# 55_VO-HDMI1_4_TX_MIPI_to_HDMI.net
KiCad netlist of a schematic drawn in Altium Designer
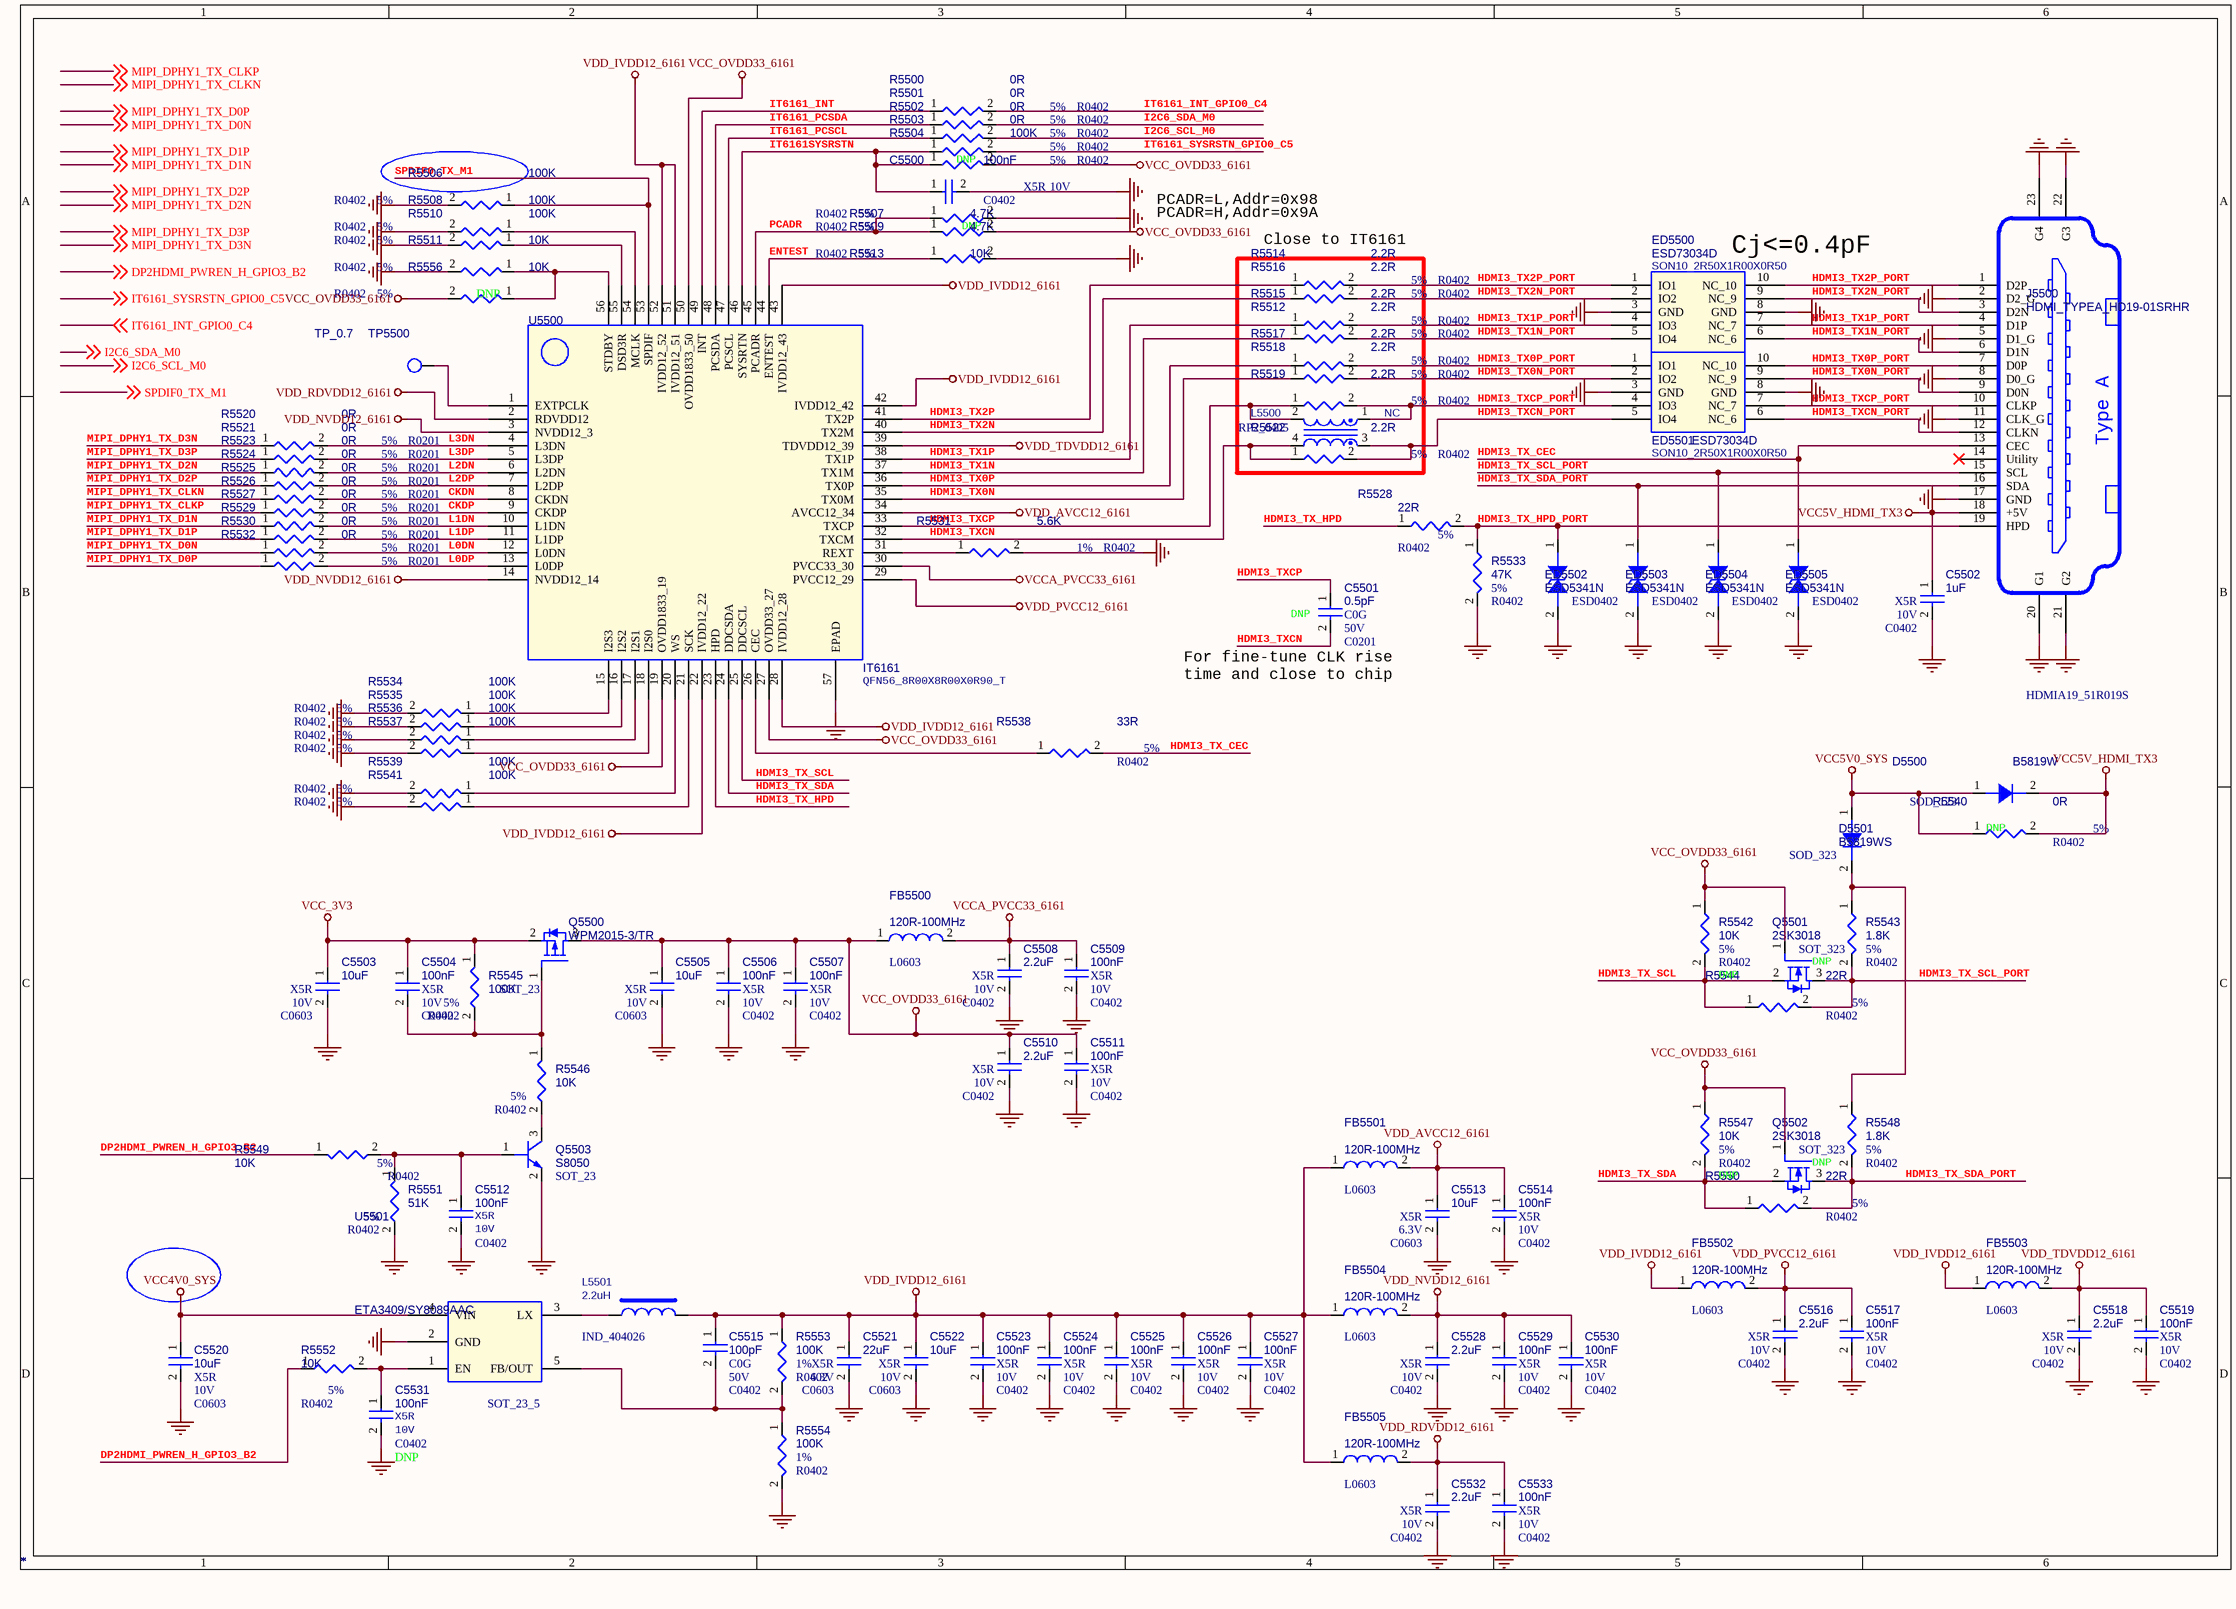
[diagram p0: 55.VO-HDMI1.4 TX(MIPI to HDMI).SchDoc]

(export (version "E")
  (design (tool "Eeschema 10.0.6"))
  (components
    (comp (ref "C5500")
      (value "*")
      (footprint "C0402")
      (description "cap,100.00nF,+/-10%,10V,X5R,C0402")
      (fields
        (field (name "VOLTAGE") "10V")
        (field (name "PCB FOOTPRINT") "C0402")
        (field (name "DIELECTRIC") "X5R")
        (field (name "MANUFACTURER") "TDK")
        (field (name "TOLERANCE") "10%")
        (field (name "ALTIUM_UNNAMED_1") "100nF")
        (field (name "CREATED BY") "JJJ")
      )
      (libsource (lib "*") (part "CAP NP"))
    )
    (comp (ref "C5501")
      (value "*")
      (footprint "C0201")
      (description "cap,0.50pF,+/-0.25,50V,C0G,C0201")
      (fields
        (field (name "VOLTAGE") "50V")
        (field (name "PCB FOOTPRINT") "C0201")
        (field (name "DIELECTRIC") "C0G")
        (field (name "OPTION") "DNP")
        (field (name "TOLERANCE") "+/-0.25pF")
        (field (name "MANUFACTURER") "TDK")
        (field (name "ALTIUM_UNNAMED_1") "0.5pF")
        (field (name "CREATED BY") "JJJ")
      )
      (libsource (lib "*") (part "CAP NP"))
    )
    (comp (ref "C5502")
      (value "*")
      (footprint "C0402")
      (description "cap,1.00uF,+/-10%,10V,X5R,C0402")
      (fields
        (field (name "VOLTAGE") "10V")
        (field (name "PCB FOOTPRINT") "C0402")
        (field (name "DIELECTRIC") "X5R")
        (field (name "TOLERANCE") "10%")
        (field (name "MANUFACTURER") "TDK")
        (field (name "ALTIUM_UNNAMED_1") "1uF")
        (field (name "CREATED BY") "JJJ")
      )
      (libsource (lib "*") (part "CAP NP"))
    )
    (comp (ref "C5503")
      (value "*")
      (footprint "C0603")
      (description "cap,10.00uF,+/-10%,10V,X5R,C0603")
      (fields
        (field (name "VOLTAGE") "10V")
        (field (name "PCB FOOTPRINT") "C0603")
        (field (name "DIELECTRIC") "X5R")
        (field (name "MANUFACTURER") "TDK")
        (field (name "TOLERANCE") "10%")
        (field (name "ALTIUM_UNNAMED_1") "10uF")
        (field (name "CREATED BY") "JJJ")
      )
      (libsource (lib "*") (part "CAP NP"))
    )
    (comp (ref "C5504")
      (value "*")
      (footprint "C0402")
      (description "cap,100.00nF,+/-10%,10V,X5R,C0402")
      (fields
        (field (name "VOLTAGE") "10V")
        (field (name "PCB FOOTPRINT") "C0402")
        (field (name "DIELECTRIC") "X5R")
        (field (name "TOLERANCE") "10%")
        (field (name "MANUFACTURER") "TDK")
        (field (name "ALTIUM_UNNAMED_1") "100nF")
        (field (name "CREATED BY") "JJJ")
      )
      (libsource (lib "*") (part "CAP NP"))
    )
    (comp (ref "C5505")
      (value "*")
      (footprint "C0603")
      (description "cap,10.00uF,+/-10%,10V,X5R,C0603")
      (fields
        (field (name "VOLTAGE") "10V")
        (field (name "PCB FOOTPRINT") "C0603")
        (field (name "DIELECTRIC") "X5R")
        (field (name "MANUFACTURER") "TDK")
        (field (name "TOLERANCE") "10%")
        (field (name "ALTIUM_UNNAMED_1") "10uF")
        (field (name "CREATED BY") "JJJ")
      )
      (libsource (lib "*") (part "CAP NP"))
    )
    (comp (ref "C5506")
      (value "*")
      (footprint "C0402")
      (description "cap,100.00nF,+/-10%,10V,X5R,C0402")
      (fields
        (field (name "VOLTAGE") "10V")
        (field (name "PCB FOOTPRINT") "C0402")
        (field (name "DIELECTRIC") "X5R")
        (field (name "TOLERANCE") "10%")
        (field (name "MANUFACTURER") "TDK")
        (field (name "ALTIUM_UNNAMED_1") "100nF")
        (field (name "CREATED BY") "JJJ")
      )
      (libsource (lib "*") (part "CAP NP"))
    )
    (comp (ref "C5507")
      (value "*")
      (footprint "C0402")
      (description "cap,100.00nF,+/-10%,10V,X5R,C0402")
      (fields
        (field (name "VOLTAGE") "10V")
        (field (name "PCB FOOTPRINT") "C0402")
        (field (name "DIELECTRIC") "X5R")
        (field (name "TOLERANCE") "10%")
        (field (name "MANUFACTURER") "TDK")
        (field (name "ALTIUM_UNNAMED_1") "100nF")
        (field (name "CREATED BY") "JJJ")
      )
      (libsource (lib "*") (part "CAP NP"))
    )
    (comp (ref "C5508")
      (value "*")
      (footprint "C0402")
      (description "cap,2.20uF,+/-10%,10V,X5R,C0402")
      (fields
        (field (name "VOLTAGE") "10V")
        (field (name "PCB FOOTPRINT") "C0402")
        (field (name "DIELECTRIC") "X5R")
        (field (name "TOLERANCE") "10%")
        (field (name "MANUFACTURER") "TDK")
        (field (name "ALTIUM_UNNAMED_1") "2.2uF")
        (field (name "CREATED BY") "JJJ")
      )
      (libsource (lib "*") (part "CAP NP"))
    )
    (comp (ref "C5509")
      (value "*")
      (footprint "C0402")
      (description "cap,100.00nF,+/-10%,10V,X5R,C0402")
      (fields
        (field (name "VOLTAGE") "10V")
        (field (name "PCB FOOTPRINT") "C0402")
        (field (name "DIELECTRIC") "X5R")
        (field (name "TOLERANCE") "10%")
        (field (name "MANUFACTURER") "TDK")
        (field (name "ALTIUM_UNNAMED_1") "100nF")
        (field (name "CREATED BY") "JJJ")
      )
      (libsource (lib "*") (part "CAP NP"))
    )
    (comp (ref "C5510")
      (value "*")
      (footprint "C0402")
      (description "cap,2.20uF,+/-10%,10V,X5R,C0402")
      (fields
        (field (name "VOLTAGE") "10V")
        (field (name "PCB FOOTPRINT") "C0402")
        (field (name "DIELECTRIC") "X5R")
        (field (name "TOLERANCE") "10%")
        (field (name "MANUFACTURER") "TDK")
        (field (name "ALTIUM_UNNAMED_1") "2.2uF")
        (field (name "CREATED BY") "JJJ")
      )
      (libsource (lib "*") (part "CAP NP"))
    )
    (comp (ref "C5511")
      (value "*")
      (footprint "C0402")
      (description "cap,100.00nF,+/-10%,10V,X5R,C0402")
      (fields
        (field (name "VOLTAGE") "10V")
        (field (name "PCB FOOTPRINT") "C0402")
        (field (name "DIELECTRIC") "X5R")
        (field (name "MANUFACTURER") "TDK")
        (field (name "TOLERANCE") "10%")
        (field (name "ALTIUM_UNNAMED_1") "100nF")
        (field (name "CREATED BY") "JJJ")
      )
      (libsource (lib "*") (part "CAP NP"))
    )
    (comp (ref "C5512")
      (value "*")
      (footprint "C0402")
      (description "cap,100.00nF,+/-10%,10V,X5R,C0402")
      (fields
        (field (name "VOLTAGE") "10V")
        (field (name "PCB FOOTPRINT") "C0402")
        (field (name "DIELECTRIC") "X5R")
        (field (name "TOLERANCE") "10%")
        (field (name "MANUFACTURER") "TDK")
        (field (name "ALTIUM_UNNAMED_1") "100nF")
        (field (name "CREATED BY") "JJJ")
      )
      (libsource (lib "*") (part "CAP NP"))
    )
    (comp (ref "C5513")
      (value "*")
      (footprint "C0603")
      (description "cap,10.00uF,+/-10%,6.3V,X5R,C0603")
      (fields
        (field (name "VOLTAGE") "6.3V")
        (field (name "PCB FOOTPRINT") "C0603")
        (field (name "DIELECTRIC") "X5R")
        (field (name "MANUFACTURER") "TDK")
        (field (name "TOLERANCE") "10%")
        (field (name "ALTIUM_UNNAMED_1") "10uF")
        (field (name "CREATED BY") "JJJ")
      )
      (libsource (lib "*") (part "CAP NP"))
    )
    (comp (ref "C5514")
      (value "*")
      (footprint "C0402")
      (description "cap,100.00nF,+/-10%,10V,X5R,C0402")
      (fields
        (field (name "VOLTAGE") "10V")
        (field (name "PCB FOOTPRINT") "C0402")
        (field (name "DIELECTRIC") "X5R")
        (field (name "MANUFACTURER") "TDK")
        (field (name "TOLERANCE") "10%")
        (field (name "ALTIUM_UNNAMED_1") "100nF")
        (field (name "CREATED BY") "JJJ")
      )
      (libsource (lib "*") (part "CAP NP"))
    )
    (comp (ref "C5515")
      (value "*")
      (footprint "C0402")
      (description "cap,100.00pF,+/-10%,50V,C0G,C0402")
      (fields
        (field (name "VOLTAGE") "50V")
        (field (name "PCB FOOTPRINT") "C0402")
        (field (name "DIELECTRIC") "C0G")
        (field (name "TOLERANCE") "10%")
        (field (name "MANUFACTURER") "TDK")
        (field (name "ALTIUM_UNNAMED_1") "100pF")
        (field (name "CREATED BY") "JJJ")
      )
      (libsource (lib "*") (part "CAP NP"))
    )
    (comp (ref "C5516")
      (value "*")
      (footprint "C0402")
      (description "cap,2.20uF,+/-10%,10V,X5R,C0402")
      (fields
        (field (name "VOLTAGE") "10V")
        (field (name "PCB FOOTPRINT") "C0402")
        (field (name "DIELECTRIC") "X5R")
        (field (name "TOLERANCE") "10%")
        (field (name "MANUFACTURER") "TDK")
        (field (name "ALTIUM_UNNAMED_1") "2.2uF")
        (field (name "CREATED BY") "JJJ")
      )
      (libsource (lib "*") (part "CAP NP"))
    )
    (comp (ref "C5517")
      (value "*")
      (footprint "C0402")
      (description "cap,100.00nF,+/-10%,10V,X5R,C0402")
      (fields
        (field (name "VOLTAGE") "10V")
        (field (name "PCB FOOTPRINT") "C0402")
        (field (name "DIELECTRIC") "X5R")
        (field (name "TOLERANCE") "10%")
        (field (name "MANUFACTURER") "TDK")
        (field (name "ALTIUM_UNNAMED_1") "100nF")
        (field (name "CREATED BY") "JJJ")
      )
      (libsource (lib "*") (part "CAP NP"))
    )
    (comp (ref "C5518")
      (value "*")
      (footprint "C0402")
      (description "cap,2.20uF,+/-10%,10V,X5R,C0402")
      (fields
        (field (name "VOLTAGE") "10V")
        (field (name "PCB FOOTPRINT") "C0402")
        (field (name "DIELECTRIC") "X5R")
        (field (name "TOLERANCE") "10%")
        (field (name "MANUFACTURER") "TDK")
        (field (name "ALTIUM_UNNAMED_1") "2.2uF")
        (field (name "CREATED BY") "JJJ")
      )
      (libsource (lib "*") (part "CAP NP"))
    )
    (comp (ref "C5519")
      (value "*")
      (footprint "C0402")
      (description "cap,100.00nF,+/-10%,10V,X5R,C0402")
      (fields
        (field (name "VOLTAGE") "10V")
        (field (name "PCB FOOTPRINT") "C0402")
        (field (name "DIELECTRIC") "X5R")
        (field (name "TOLERANCE") "10%")
        (field (name "MANUFACTURER") "TDK")
        (field (name "ALTIUM_UNNAMED_1") "100nF")
        (field (name "CREATED BY") "JJJ")
      )
      (libsource (lib "*") (part "CAP NP"))
    )
    (comp (ref "C5520")
      (value "*")
      (footprint "C0603")
      (description "cap,10.00uF,+/-10%,10V,X5R,C0603")
      (fields
        (field (name "VOLTAGE") "10V")
        (field (name "PCB FOOTPRINT") "C0603")
        (field (name "DIELECTRIC") "X5R")
        (field (name "TOLERANCE") "10%")
        (field (name "MANUFACTURER") "TDK")
        (field (name "ALTIUM_UNNAMED_1") "10uF")
        (field (name "CREATED BY") "JJJ")
      )
      (libsource (lib "*") (part "CAP NP"))
    )
    (comp (ref "C5521")
      (value "*")
      (footprint "C0603")
      (description "cap,22.00uF,+/-20%,6.3V,X5R,C0603")
      (fields
        (field (name "VOLTAGE") "6.3V")
        (field (name "PCB FOOTPRINT") "C0603")
        (field (name "DIELECTRIC") "X5R")
        (field (name "TOLERANCE") "20%")
        (field (name "MANUFACTURER") "TDK")
        (field (name "ALTIUM_UNNAMED_1") "22uF")
        (field (name "CREATED BY") "JJJ")
      )
      (libsource (lib "*") (part "CAP NP"))
    )
    (comp (ref "C5522")
      (value "*")
      (footprint "C0603")
      (description "cap,10.00uF,+/-10%,10V,X5R,C0603")
      (fields
        (field (name "VOLTAGE") "10V")
        (field (name "PCB FOOTPRINT") "C0603")
        (field (name "DIELECTRIC") "X5R")
        (field (name "MANUFACTURER") "TDK")
        (field (name "TOLERANCE") "10%")
        (field (name "ALTIUM_UNNAMED_1") "10uF")
        (field (name "CREATED BY") "JJJ")
      )
      (libsource (lib "*") (part "CAP NP"))
    )
    (comp (ref "C5523")
      (value "*")
      (footprint "C0402")
      (description "cap,100.00nF,+/-10%,10V,X5R,C0402")
      (fields
        (field (name "VOLTAGE") "10V")
        (field (name "PCB FOOTPRINT") "C0402")
        (field (name "DIELECTRIC") "X5R")
        (field (name "MANUFACTURER") "TDK")
        (field (name "TOLERANCE") "10%")
        (field (name "ALTIUM_UNNAMED_1") "100nF")
        (field (name "CREATED BY") "JJJ")
      )
      (libsource (lib "*") (part "CAP NP"))
    )
    (comp (ref "C5524")
      (value "*")
      (footprint "C0402")
      (description "cap,100.00nF,+/-10%,10V,X5R,C0402")
      (fields
        (field (name "VOLTAGE") "10V")
        (field (name "PCB FOOTPRINT") "C0402")
        (field (name "DIELECTRIC") "X5R")
        (field (name "MANUFACTURER") "TDK")
        (field (name "TOLERANCE") "10%")
        (field (name "ALTIUM_UNNAMED_1") "100nF")
        (field (name "CREATED BY") "JJJ")
      )
      (libsource (lib "*") (part "CAP NP"))
    )
    (comp (ref "C5525")
      (value "*")
      (footprint "C0402")
      (description "cap,100.00nF,+/-10%,10V,X5R,C0402")
      (fields
        (field (name "VOLTAGE") "10V")
        (field (name "PCB FOOTPRINT") "C0402")
        (field (name "DIELECTRIC") "X5R")
        (field (name "TOLERANCE") "10%")
        (field (name "MANUFACTURER") "TDK")
        (field (name "ALTIUM_UNNAMED_1") "100nF")
        (field (name "CREATED BY") "JJJ")
      )
      (libsource (lib "*") (part "CAP NP"))
    )
    (comp (ref "C5526")
      (value "*")
      (footprint "C0402")
      (description "cap,100.00nF,+/-10%,10V,X5R,C0402")
      (fields
        (field (name "VOLTAGE") "10V")
        (field (name "PCB FOOTPRINT") "C0402")
        (field (name "DIELECTRIC") "X5R")
        (field (name "MANUFACTURER") "TDK")
        (field (name "TOLERANCE") "10%")
        (field (name "ALTIUM_UNNAMED_1") "100nF")
        (field (name "CREATED BY") "JJJ")
      )
      (libsource (lib "*") (part "CAP NP"))
    )
    (comp (ref "C5527")
      (value "*")
      (footprint "C0402")
      (description "cap,100.00nF,+/-10%,10V,X5R,C0402")
      (fields
        (field (name "VOLTAGE") "10V")
        (field (name "PCB FOOTPRINT") "C0402")
        (field (name "DIELECTRIC") "X5R")
        (field (name "MANUFACTURER") "TDK")
        (field (name "TOLERANCE") "10%")
        (field (name "ALTIUM_UNNAMED_1") "100nF")
        (field (name "CREATED BY") "JJJ")
      )
      (libsource (lib "*") (part "CAP NP"))
    )
    (comp (ref "C5528")
      (value "*")
      (footprint "C0402")
      (description "cap,2.20uF,+/-10%,10V,X5R,C0402")
      (fields
        (field (name "VOLTAGE") "10V")
        (field (name "PCB FOOTPRINT") "C0402")
        (field (name "DIELECTRIC") "X5R")
        (field (name "TOLERANCE") "10%")
        (field (name "MANUFACTURER") "TDK")
        (field (name "ALTIUM_UNNAMED_1") "2.2uF")
        (field (name "CREATED BY") "JJJ")
      )
      (libsource (lib "*") (part "CAP NP"))
    )
    (comp (ref "C5529")
      (value "*")
      (footprint "C0402")
      (description "cap,100.00nF,+/-10%,10V,X5R,C0402")
      (fields
        (field (name "VOLTAGE") "10V")
        (field (name "PCB FOOTPRINT") "C0402")
        (field (name "DIELECTRIC") "X5R")
        (field (name "MANUFACTURER") "TDK")
        (field (name "TOLERANCE") "10%")
        (field (name "ALTIUM_UNNAMED_1") "100nF")
        (field (name "CREATED BY") "JJJ")
      )
      (libsource (lib "*") (part "CAP NP"))
    )
    (comp (ref "C5530")
      (value "*")
      (footprint "C0402")
      (description "cap,100.00nF,+/-10%,10V,X5R,C0402")
      (fields
        (field (name "VOLTAGE") "10V")
        (field (name "PCB FOOTPRINT") "C0402")
        (field (name "DIELECTRIC") "X5R")
        (field (name "TOLERANCE") "10%")
        (field (name "MANUFACTURER") "TDK")
        (field (name "ALTIUM_UNNAMED_1") "100nF")
        (field (name "CREATED BY") "JJJ")
      )
      (libsource (lib "*") (part "CAP NP"))
    )
    (comp (ref "C5531")
      (value "*")
      (footprint "C0402")
      (description "cap,100.00nF,+/-10%,10V,X5R,C0402")
      (fields
        (field (name "VOLTAGE") "10V")
        (field (name "PCB FOOTPRINT") "C0402")
        (field (name "DIELECTRIC") "X5R")
        (field (name "TOLERANCE") "10%")
        (field (name "MANUFACTURER") "TDK")
        (field (name "OPTION") "DNP")
        (field (name "ALTIUM_UNNAMED_1") "100nF")
        (field (name "CREATED BY") "JJJ")
      )
      (libsource (lib "*") (part "CAP NP"))
    )
    (comp (ref "C5532")
      (value "*")
      (footprint "C0402")
      (description "cap,2.20uF,+/-10%,10V,X5R,C0402")
      (fields
        (field (name "VOLTAGE") "10V")
        (field (name "PCB FOOTPRINT") "C0402")
        (field (name "DIELECTRIC") "X5R")
        (field (name "MANUFACTURER") "TDK")
        (field (name "TOLERANCE") "10%")
        (field (name "ALTIUM_UNNAMED_1") "2.2uF")
        (field (name "CREATED BY") "JJJ")
      )
      (libsource (lib "*") (part "CAP NP"))
    )
    (comp (ref "C5533")
      (value "*")
      (footprint "C0402")
      (description "cap,100.00nF,+/-10%,10V,X5R,C0402")
      (fields
        (field (name "VOLTAGE") "10V")
        (field (name "PCB FOOTPRINT") "C0402")
        (field (name "DIELECTRIC") "X5R")
        (field (name "MANUFACTURER") "TDK")
        (field (name "TOLERANCE") "10%")
        (field (name "ALTIUM_UNNAMED_1") "100nF")
        (field (name "CREATED BY") "JJJ")
      )
      (libsource (lib "*") (part "CAP NP"))
    )
    (comp (ref "D5500")
      (value "*")
      (footprint "SOD_123")
      (description "Schottky BarrierЈ¬B5819W SOD-123")
      (fields
        (field (name "PCB FOOTPRINT") "SOD_123")
        (field (name "MANUFACTURER") "і¤µз")
        (field (name "ALTIUM_UNNAMED_1") "B5819W")
        (field (name "CREATED BY") "JJJ")
      )
      (libsource (lib "*") (part "DIODE"))
    )
    (comp (ref "D5501")
      (value "*")
      (footprint "SOD_323")
      (description "Schottky BarrierЈ¬B5819WS SOD-323")
      (fields
        (field (name "PCB FOOTPRINT") "SOD_323")
        (field (name "MANUFACTURER") "і¤µз")
        (field (name "ALTIUM_UNNAMED_1") "B5819WS")
        (field (name "CREATED BY") "JJJ")
      )
      (libsource (lib "*") (part "DIODE"))
    )
    (comp (ref "ED5500")
      (value "*")
      (footprint "SON10_2R50X1R00X0R50")
      (description "4-Lines, Uni-directional, Ultra-low Capacitance Transient Voltage Suppressors")
      (fields
        (field (name "PCB FOOTPRINT") "SON10_2R50X1R00X0R50")
        (field (name "MANUFACTURER") "WillSemi(О¤¶ы°лµјМе)")
        (field (name "ALTIUM_UNNAMED_1") "ESD73034D")
        (field (name "CREATED BY") "JJJ")
      )
      (libsource (lib "*") (part "ESD_ESD5304D"))
    )
    (comp (ref "ED5501")
      (value "*")
      (footprint "SON10_2R50X1R00X0R50")
      (description "4-Lines, Uni-directional, Ultra-low Capacitance Transient Voltage Suppressors")
      (fields
        (field (name "PCB FOOTPRINT") "SON10_2R50X1R00X0R50")
        (field (name "MANUFACTURER") "WillSemi(О¤¶ы°лµјМе)")
        (field (name "ALTIUM_UNNAMED_1") "ESD73034D")
        (field (name "CREATED BY") "JJJ")
      )
      (libsource (lib "*") (part "ESD_ESD5304D"))
    )
    (comp (ref "ED5502")
      (value "*")
      (footprint "ESD0402")
      (description "1-Line, Bi-directional, Transient Voltage Suppressors.1pF.")
      (fields
        (field (name "PCB FOOTPRINT") "ESD0402")
        (field (name "MANUFACTURER") "WillSemi(О¤¶ы°лµјМе)")
        (field (name "ALTIUM_UNNAMED_1") "ESD5341N")
        (field (name "CREATED BY") "JJJ")
      )
      (libsource (lib "*") (part "DIODE BI_DIR TRIG"))
    )
    (comp (ref "ED5503")
      (value "*")
      (footprint "ESD0402")
      (description "1-Line, Bi-directional, Transient Voltage Suppressors.1pF.")
      (fields
        (field (name "PCB FOOTPRINT") "ESD0402")
        (field (name "MANUFACTURER") "WillSemi(О¤¶ы°лµјМе)")
        (field (name "ALTIUM_UNNAMED_1") "ESD5341N")
        (field (name "CREATED BY") "JJJ")
      )
      (libsource (lib "*") (part "DIODE BI_DIR TRIG"))
    )
    (comp (ref "ED5504")
      (value "*")
      (footprint "ESD0402")
      (description "1-Line, Bi-directional, Transient Voltage Suppressors.1pF.")
      (fields
        (field (name "PCB FOOTPRINT") "ESD0402")
        (field (name "MANUFACTURER") "WillSemi(О¤¶ы°лµјМе)")
        (field (name "ALTIUM_UNNAMED_1") "ESD5341N")
        (field (name "CREATED BY") "JJJ")
      )
      (libsource (lib "*") (part "DIODE BI_DIR TRIG"))
    )
    (comp (ref "ED5505")
      (value "*")
      (footprint "ESD0402")
      (description "1-Line, Bi-directional, Transient Voltage Suppressors.1pF.")
      (fields
        (field (name "PCB FOOTPRINT") "ESD0402")
        (field (name "MANUFACTURER") "WillSemi(О¤¶ы°лµјМе)")
        (field (name "ALTIUM_UNNAMED_1") "ESD5341N")
        (field (name "CREATED BY") "JJJ")
      )
      (libsource (lib "*") (part "DIODE BI_DIR TRIG"))
    )
    (comp (ref "FB5500")
      (value "*")
      (footprint "L0603")
      (description "BEAD,120R@100MHz,current=2000mA,0603")
      (fields
        (field (name "TOLERANCE") "25%")
        (field (name "PCB FOOTPRINT") "L0603")
        (field (name "MANUFACTURER") "Murata")
        (field (name "ALTIUM_UNNAMED_1") "120R-100MHz")
        (field (name "CREATED BY") "DZS")
      )
      (libsource (lib "*") (part "BEAD"))
    )
    (comp (ref "FB5501")
      (value "*")
      (footprint "L0603")
      (description "BEAD,120R@100MHz,current=2000mA,0603")
      (fields
        (field (name "TOLERANCE") "25%")
        (field (name "PCB FOOTPRINT") "L0603")
        (field (name "MANUFACTURER") "Murata")
        (field (name "ALTIUM_UNNAMED_1") "120R-100MHz")
        (field (name "CREATED BY") "DZS")
      )
      (libsource (lib "*") (part "BEAD"))
    )
    (comp (ref "FB5502")
      (value "*")
      (footprint "L0603")
      (description "BEAD,120R@100MHz,current=2000mA,0603")
      (fields
        (field (name "TOLERANCE") "25%")
        (field (name "PCB FOOTPRINT") "L0603")
        (field (name "MANUFACTURER") "Murata")
        (field (name "ALTIUM_UNNAMED_1") "120R-100MHz")
        (field (name "CREATED BY") "DZS")
      )
      (libsource (lib "*") (part "BEAD"))
    )
    (comp (ref "FB5503")
      (value "*")
      (footprint "L0603")
      (description "BEAD,120R@100MHz,current=2000mA,0603")
      (fields
        (field (name "TOLERANCE") "25%")
        (field (name "PCB FOOTPRINT") "L0603")
        (field (name "MANUFACTURER") "Murata")
        (field (name "ALTIUM_UNNAMED_1") "120R-100MHz")
        (field (name "CREATED BY") "DZS")
      )
      (libsource (lib "*") (part "BEAD"))
    )
    (comp (ref "FB5504")
      (value "*")
      (footprint "L0603")
      (description "BEAD,120R@100MHz,current=2000mA,0603")
      (fields
        (field (name "TOLERANCE") "25%")
        (field (name "PCB FOOTPRINT") "L0603")
        (field (name "MANUFACTURER") "Murata")
        (field (name "ALTIUM_UNNAMED_1") "120R-100MHz")
        (field (name "CREATED BY") "DZS")
      )
      (libsource (lib "*") (part "BEAD"))
    )
    (comp (ref "FB5505")
      (value "*")
      (footprint "L0603")
      (description "BEAD,120R@100MHz,current=2000mA,0603")
      (fields
        (field (name "TOLERANCE") "25%")
        (field (name "PCB FOOTPRINT") "L0603")
        (field (name "MANUFACTURER") "Murata")
        (field (name "ALTIUM_UNNAMED_1") "120R-100MHz")
        (field (name "CREATED BY") "DZS")
      )
      (libsource (lib "*") (part "BEAD"))
    )
    (comp (ref "J5500")
      (value "*")
      (footprint "HDMIA19_51R019S")
      (fields
        (field (name "PCB FOOTPRINT") "HDMIA19_51R019S")
        (field (name "ALTIUM_UNNAMED_1") "HDMI_TYPEA_HD19-01SRHR")
      )
      (libsource (lib "*") (part "HDMI_TYPE_A_0"))
    )
    (comp (ref "L5500")
      (value "*")
      (footprint "L0402D")
      (description "Winding Type Common Mode Choke Coil")
      (fields
        (field (name "PCB FOOTPRINT") "RP2_0405")
        (field (name "MANUFACTURER") "sunlord")
        (field (name "TOLERANCE") "25%")
        (field (name "ALTIUM_UNNAMED_1") "NC")
        (field (name "CREATED BY") "JJJ")
      )
      (libsource (lib "*") (part "INDUCTOR COM"))
    )
    (comp (ref "L5501")
      (value "*")
      (footprint "IND_404026")
      (description "Power Inductor,2.2uH,0.2,IND_404026")
      (fields
        (field (name "PCB FOOTPRINT") "IND_404026")
        (field (name "MANUFACTURER") "sunlord")
        (field (name "TOLERANCE") "20%")
        (field (name "ALTIUM_UNNAMED_1") "2.2uH")
        (field (name "CREATED BY") "YTL")
      )
      (libsource (lib "*") (part "INDUCTORS OF FERRITE_Dup1"))
    )
    (comp (ref "Q5500")
      (value "*")
      (footprint "SOT23")
      (description "PMOS,WPM2015-3/TR,SOT_23,Id=2.4A,Vds=20V")
      (fields
        (field (name "PCB FOOTPRINT") "SOT_23")
        (field (name "MANUFACTURER") "WillSemi(О¤¶ы°лµјМе)")
        (field (name "ALTIUM_UNNAMED_1") "WPM2015-3/TR")
        (field (name "CREATED BY") "JJJ")
      )
      (libsource (lib "*") (part "MOSFET P"))
    )
    (comp (ref "Q5501")
      (value "*")
      (footprint "SOT23")
      (description "NMOS,2SK3018,SOT_323,Id=0.1A,Vds=30V")
      (fields
        (field (name "PCB FOOTPRINT") "SOT_323")
        (field (name "OPTION") "DNP")
        (field (name "MANUFACTURER") "ROHM")
        (field (name "ALTIUM_UNNAMED_1") "2SK3018")
        (field (name "CREATED BY") "JJJ")
      )
      (libsource (lib "*") (part "MOSFET N"))
    )
    (comp (ref "Q5502")
      (value "*")
      (footprint "SOT23")
      (description "NMOS,2SK3018,SOT_323,Id=0.1A,Vds=30V")
      (fields
        (field (name "PCB FOOTPRINT") "SOT_323")
        (field (name "OPTION") "DNP")
        (field (name "MANUFACTURER") "ROHM")
        (field (name "ALTIUM_UNNAMED_1") "2SK3018")
        (field (name "CREATED BY") "JJJ")
      )
      (libsource (lib "*") (part "MOSFET N"))
    )
    (comp (ref "Q5503")
      (value "*")
      (footprint "SOT_23")
      (description "S8050,SOT23")
      (fields
        (field (name "PCB FOOTPRINT") "SOT_23")
        (field (name "MANUFACTURER") "і¤µз")
        (field (name "ALTIUM_UNNAMED_1") "S8050")
        (field (name "CREATED BY") "JJJ")
      )
      (libsource (lib "*") (part "NPN"))
    )
    (comp (ref "R5500")
      (value "*")
      (footprint "R0402")
      (description "НЁУГєсД¤µзЧи,0R,+/-5%,R0402,1/16W.")
      (fields
        (field (name "PCB FOOTPRINT") "R0402")
        (field (name "TOLERANCE") "5%")
        (field (name "MANUFACTURER") "YAGEO")
        (field (name "ALTIUM_UNNAMED_1") "0R")
        (field (name "CREATED BY") "YTL")
      )
      (libsource (lib "*") (part "RESISTOR_Dup1"))
    )
    (comp (ref "R5501")
      (value "*")
      (footprint "R0402")
      (description "НЁУГєсД¤µзЧи,0R,+/-5%,R0402,1/16W.")
      (fields
        (field (name "PCB FOOTPRINT") "R0402")
        (field (name "TOLERANCE") "5%")
        (field (name "MANUFACTURER") "YAGEO")
        (field (name "ALTIUM_UNNAMED_1") "0R")
        (field (name "CREATED BY") "YTL")
      )
      (libsource (lib "*") (part "RESISTOR_Dup1"))
    )
    (comp (ref "R5502")
      (value "*")
      (footprint "R0402")
      (description "НЁУГєсД¤µзЧи,0R,+/-5%,R0402,1/16W.")
      (fields
        (field (name "PCB FOOTPRINT") "R0402")
        (field (name "TOLERANCE") "5%")
        (field (name "MANUFACTURER") "YAGEO")
        (field (name "ALTIUM_UNNAMED_1") "0R")
        (field (name "CREATED BY") "YTL")
      )
      (libsource (lib "*") (part "RESISTOR_Dup1"))
    )
    (comp (ref "R5503")
      (value "*")
      (footprint "R0402")
      (description "НЁУГєсД¤µзЧи,0R,+/-5%,R0402,1/16W.")
      (fields
        (field (name "PCB FOOTPRINT") "R0402")
        (field (name "TOLERANCE") "5%")
        (field (name "MANUFACTURER") "YAGEO")
        (field (name "ALTIUM_UNNAMED_1") "0R")
        (field (name "CREATED BY") "YTL")
      )
      (libsource (lib "*") (part "RESISTOR_Dup1"))
    )
    (comp (ref "R5504")
      (value "*")
      (footprint "R0402")
      (description "НЁУГєсД¤µзЧи,100K,+/-5%,R0402,1/16W.")
      (fields
        (field (name "PCB FOOTPRINT") "R0402")
        (field (name "TOLERANCE") "5%")
        (field (name "MANUFACTURER") "YAGEO")
        (field (name "OPTION") "DNP")
        (field (name "ALTIUM_UNNAMED_1") "100K")
        (field (name "CREATED BY") "YTL")
      )
      (libsource (lib "*") (part "RESISTOR_Dup1"))
    )
    (comp (ref "R5506")
      (value "*")
      (footprint "R0402")
      (description "НЁУГєсД¤µзЧи,100K,+/-5%,R0402,1/16W.")
      (fields
        (field (name "PCB FOOTPRINT") "R0402")
        (field (name "TOLERANCE") "5%")
        (field (name "MANUFACTURER") "YAGEO")
        (field (name "ALTIUM_UNNAMED_1") "100K")
        (field (name "CREATED BY") "YTL")
      )
      (libsource (lib "*") (part "RESISTOR_Dup1"))
    )
    (comp (ref "R5507")
      (value "*")
      (footprint "R0402")
      (description "НЁУГєсД¤µзЧи,4K7,+/-5%,R0402,1/16W.")
      (fields
        (field (name "PCB FOOTPRINT") "R0402")
        (field (name "TOLERANCE") "5%")
        (field (name "MANUFACTURER") "YAGEO")
        (field (name "ALTIUM_UNNAMED_1") "4.7K")
        (field (name "CREATED BY") "YTL")
      )
      (libsource (lib "*") (part "RESISTOR_Dup1"))
    )
    (comp (ref "R5508")
      (value "*")
      (footprint "R0402")
      (description "НЁУГєсД¤µзЧи,100K,+/-5%,R0402,1/16W.")
      (fields
        (field (name "PCB FOOTPRINT") "R0402")
        (field (name "TOLERANCE") "5%")
        (field (name "MANUFACTURER") "YAGEO")
        (field (name "ALTIUM_UNNAMED_1") "100K")
        (field (name "CREATED BY") "YTL")
      )
      (libsource (lib "*") (part "RESISTOR_Dup1"))
    )
    (comp (ref "R5509")
      (value "*")
      (footprint "R0402")
      (description "НЁУГєсД¤µзЧи,4K7,+/-5%,R0402,1/16W.")
      (fields
        (field (name "PCB FOOTPRINT") "R0402")
        (field (name "TOLERANCE") "5%")
        (field (name "OPTION") "DNP")
        (field (name "MANUFACTURER") "YAGEO")
        (field (name "ALTIUM_UNNAMED_1") "4.7K")
        (field (name "CREATED BY") "YTL")
      )
      (libsource (lib "*") (part "RESISTOR_Dup1"))
    )
    (comp (ref "R5510")
      (value "*")
      (footprint "R0402")
      (description "НЁУГєсД¤µзЧи,100K,+/-5%,R0402,1/16W.")
      (fields
        (field (name "PCB FOOTPRINT") "R0402")
        (field (name "TOLERANCE") "5%")
        (field (name "MANUFACTURER") "YAGEO")
        (field (name "ALTIUM_UNNAMED_1") "100K")
        (field (name "CREATED BY") "YTL")
      )
      (libsource (lib "*") (part "RESISTOR_Dup1"))
    )
    (comp (ref "R5511")
      (value "*")
      (footprint "R0402")
      (description "НЁУГєсД¤µзЧи,10K,+/-5%,R0402,1/16W.")
      (fields
        (field (name "PCB FOOTPRINT") "R0402")
        (field (name "TOLERANCE") "5%")
        (field (name "MANUFACTURER") "YAGEO")
        (field (name "ALTIUM_UNNAMED_1") "10K")
        (field (name "CREATED BY") "YTL")
      )
      (libsource (lib "*") (part "RESISTOR_Dup1"))
    )
    (comp (ref "R5512")
      (value "*")
      (footprint "R0402")
      (description "НЁУГєсД¤µзЧи,2R2,+/-5%,R0402,1/16W.")
      (fields
        (field (name "PCB FOOTPRINT") "R0402")
        (field (name "TOLERANCE") "5%")
        (field (name "MANUFACTURER") "YAGEO")
        (field (name "ALTIUM_UNNAMED_1") "2.2R")
        (field (name "CREATED BY") "YTL")
      )
      (libsource (lib "*") (part "RESISTOR_Dup1"))
    )
    (comp (ref "R5513")
      (value "*")
      (footprint "R0402")
      (description "НЁУГєсД¤µзЧи,10K,+/-5%,R0402,1/16W.")
      (fields
        (field (name "PCB FOOTPRINT") "R0402")
        (field (name "TOLERANCE") "5%")
        (field (name "MANUFACTURER") "YAGEO")
        (field (name "ALTIUM_UNNAMED_1") "10K")
        (field (name "CREATED BY") "YTL")
      )
      (libsource (lib "*") (part "RESISTOR_Dup1"))
    )
    (comp (ref "R5514")
      (value "*")
      (footprint "R0402")
      (description "НЁУГєсД¤µзЧи,2R2,+/-5%,R0402,1/16W.")
      (fields
        (field (name "PCB FOOTPRINT") "R0402")
        (field (name "TOLERANCE") "5%")
        (field (name "MANUFACTURER") "YAGEO")
        (field (name "ALTIUM_UNNAMED_1") "2.2R")
        (field (name "CREATED BY") "YTL")
      )
      (libsource (lib "*") (part "RESISTOR_Dup1"))
    )
    (comp (ref "R5515")
      (value "*")
      (footprint "R0402")
      (description "НЁУГєсД¤µзЧи,2R2,+/-5%,R0402,1/16W.")
      (fields
        (field (name "PCB FOOTPRINT") "R0402")
        (field (name "TOLERANCE") "5%")
        (field (name "MANUFACTURER") "YAGEO")
        (field (name "ALTIUM_UNNAMED_1") "2.2R")
        (field (name "CREATED BY") "YTL")
      )
      (libsource (lib "*") (part "RESISTOR_Dup1"))
    )
    (comp (ref "R5516")
      (value "*")
      (footprint "R0402")
      (description "НЁУГєсД¤µзЧи,2R2,+/-5%,R0402,1/16W.")
      (fields
        (field (name "PCB FOOTPRINT") "R0402")
        (field (name "TOLERANCE") "5%")
        (field (name "MANUFACTURER") "YAGEO")
        (field (name "ALTIUM_UNNAMED_1") "2.2R")
        (field (name "CREATED BY") "YTL")
      )
      (libsource (lib "*") (part "RESISTOR_Dup1"))
    )
    (comp (ref "R5517")
      (value "*")
      (footprint "R0402")
      (description "НЁУГєсД¤µзЧи,2R2,+/-5%,R0402,1/16W.")
      (fields
        (field (name "PCB FOOTPRINT") "R0402")
        (field (name "TOLERANCE") "5%")
        (field (name "MANUFACTURER") "YAGEO")
        (field (name "ALTIUM_UNNAMED_1") "2.2R")
        (field (name "CREATED BY") "YTL")
      )
      (libsource (lib "*") (part "RESISTOR_Dup1"))
    )
    (comp (ref "R5518")
      (value "*")
      (footprint "R0402")
      (description "НЁУГєсД¤µзЧи,2R2,+/-5%,R0402,1/16W.")
      (fields
        (field (name "PCB FOOTPRINT") "R0402")
        (field (name "TOLERANCE") "5%")
        (field (name "MANUFACTURER") "YAGEO")
        (field (name "ALTIUM_UNNAMED_1") "2.2R")
        (field (name "CREATED BY") "YTL")
      )
      (libsource (lib "*") (part "RESISTOR_Dup1"))
    )
    (comp (ref "R5519")
      (value "*")
      (footprint "R0402")
      (description "НЁУГєсД¤µзЧи,2R2,+/-5%,R0402,1/16W.")
      (fields
        (field (name "PCB FOOTPRINT") "R0402")
        (field (name "TOLERANCE") "5%")
        (field (name "MANUFACTURER") "YAGEO")
        (field (name "ALTIUM_UNNAMED_1") "2.2R")
        (field (name "CREATED BY") "YTL")
      )
      (libsource (lib "*") (part "RESISTOR_Dup1"))
    )
    (comp (ref "R5520")
      (value "*")
      (footprint "R0402")
      (description "НЁУГєсД¤µзЧи,0R,+/-5%,R0201,1/20W.")
      (fields
        (field (name "PCB FOOTPRINT") "R0201")
        (field (name "TOLERANCE") "5%")
        (field (name "MANUFACTURER") "YAGEO")
        (field (name "ALTIUM_UNNAMED_1") "0R")
        (field (name "CREATED BY") "YTL")
      )
      (libsource (lib "*") (part "RESISTOR_Dup1"))
    )
    (comp (ref "R5521")
      (value "*")
      (footprint "R0402")
      (description "НЁУГєсД¤µзЧи,0R,+/-5%,R0201,1/20W.")
      (fields
        (field (name "PCB FOOTPRINT") "R0201")
        (field (name "TOLERANCE") "5%")
        (field (name "MANUFACTURER") "YAGEO")
        (field (name "ALTIUM_UNNAMED_1") "0R")
        (field (name "CREATED BY") "YTL")
      )
      (libsource (lib "*") (part "RESISTOR_Dup1"))
    )
    (comp (ref "R5522")
      (value "*")
      (footprint "R0402")
      (description "НЁУГєсД¤µзЧи,2R2,+/-5%,R0402,1/16W.")
      (fields
        (field (name "PCB FOOTPRINT") "R0402")
        (field (name "TOLERANCE") "5%")
        (field (name "MANUFACTURER") "YAGEO")
        (field (name "ALTIUM_UNNAMED_1") "2.2R")
        (field (name "CREATED BY") "YTL")
      )
      (libsource (lib "*") (part "RESISTOR_Dup1"))
    )
    (comp (ref "R5523")
      (value "*")
      (footprint "R0402")
      (description "НЁУГєсД¤µзЧи,0R,+/-5%,R0201,1/20W.")
      (fields
        (field (name "PCB FOOTPRINT") "R0201")
        (field (name "TOLERANCE") "5%")
        (field (name "MANUFACTURER") "YAGEO")
        (field (name "ALTIUM_UNNAMED_1") "0R")
        (field (name "CREATED BY") "YTL")
      )
      (libsource (lib "*") (part "RESISTOR_Dup1"))
    )
    (comp (ref "R5524")
      (value "*")
      (footprint "R0402")
      (description "НЁУГєсД¤µзЧи,0R,+/-5%,R0201,1/20W.")
      (fields
        (field (name "PCB FOOTPRINT") "R0201")
        (field (name "TOLERANCE") "5%")
        (field (name "MANUFACTURER") "YAGEO")
        (field (name "ALTIUM_UNNAMED_1") "0R")
        (field (name "CREATED BY") "YTL")
      )
      (libsource (lib "*") (part "RESISTOR_Dup1"))
    )
    (comp (ref "R5525")
      (value "*")
      (footprint "R0402")
      (description "НЁУГєсД¤µзЧи,0R,+/-5%,R0201,1/20W.")
      (fields
        (field (name "PCB FOOTPRINT") "R0201")
        (field (name "TOLERANCE") "5%")
        (field (name "MANUFACTURER") "YAGEO")
        (field (name "ALTIUM_UNNAMED_1") "0R")
        (field (name "CREATED BY") "YTL")
      )
      (libsource (lib "*") (part "RESISTOR_Dup1"))
    )
    (comp (ref "R5526")
      (value "*")
      (footprint "R0402")
      (description "НЁУГєсД¤µзЧи,0R,+/-5%,R0201,1/20W.")
      (fields
        (field (name "PCB FOOTPRINT") "R0201")
        (field (name "TOLERANCE") "5%")
        (field (name "MANUFACTURER") "YAGEO")
        (field (name "ALTIUM_UNNAMED_1") "0R")
        (field (name "CREATED BY") "YTL")
      )
      (libsource (lib "*") (part "RESISTOR_Dup1"))
    )
    (comp (ref "R5527")
      (value "*")
      (footprint "R0402")
      (description "НЁУГєсД¤µзЧи,0R,+/-5%,R0201,1/20W.")
      (fields
        (field (name "PCB FOOTPRINT") "R0201")
        (field (name "TOLERANCE") "5%")
        (field (name "MANUFACTURER") "YAGEO")
        (field (name "ALTIUM_UNNAMED_1") "0R")
        (field (name "CREATED BY") "YTL")
      )
      (libsource (lib "*") (part "RESISTOR_Dup1"))
    )
    (comp (ref "R5528")
      (value "*")
      (footprint "R0402")
      (description "НЁУГєсД¤µзЧи,22R,+/-5%,R0402,1/16W.")
      (fields
        (field (name "PCB FOOTPRINT") "R0402")
        (field (name "TOLERANCE") "5%")
        (field (name "MANUFACTURER") "YAGEO")
        (field (name "ALTIUM_UNNAMED_1") "22R")
        (field (name "CREATED BY") "YTL")
      )
      (libsource (lib "*") (part "RESISTOR_Dup1"))
    )
    (comp (ref "R5529")
      (value "*")
      (footprint "R0402")
      (description "НЁУГєсД¤µзЧи,0R,+/-5%,R0201,1/20W.")
      (fields
        (field (name "PCB FOOTPRINT") "R0201")
        (field (name "TOLERANCE") "5%")
        (field (name "MANUFACTURER") "YAGEO")
        (field (name "ALTIUM_UNNAMED_1") "0R")
        (field (name "CREATED BY") "YTL")
      )
      (libsource (lib "*") (part "RESISTOR_Dup1"))
    )
    (comp (ref "R5530")
      (value "*")
      (footprint "R0402")
      (description "НЁУГєсД¤µзЧи,0R,+/-5%,R0201,1/20W.")
      (fields
        (field (name "PCB FOOTPRINT") "R0201")
        (field (name "TOLERANCE") "5%")
        (field (name "MANUFACTURER") "YAGEO")
        (field (name "ALTIUM_UNNAMED_1") "0R")
        (field (name "CREATED BY") "YTL")
      )
      (libsource (lib "*") (part "RESISTOR_Dup1"))
    )
    (comp (ref "R5531")
      (value "*")
      (footprint "R0402")
      (description "НЁУГєсД¤µзЧи,5K6,+/-1%,R0402,1/16W.")
      (fields
        (field (name "PCB FOOTPRINT") "R0402")
        (field (name "TOLERANCE") "1%")
        (field (name "MANUFACTURER") "YAGEO")
        (field (name "ALTIUM_UNNAMED_1") "5.6K")
        (field (name "CREATED BY") "YTL")
      )
      (libsource (lib "*") (part "RESISTOR_Dup1"))
    )
    (comp (ref "R5532")
      (value "*")
      (footprint "R0402")
      (description "НЁУГєсД¤µзЧи,0R,+/-5%,R0201,1/20W.")
      (fields
        (field (name "PCB FOOTPRINT") "R0201")
        (field (name "TOLERANCE") "5%")
        (field (name "MANUFACTURER") "YAGEO")
        (field (name "ALTIUM_UNNAMED_1") "0R")
        (field (name "CREATED BY") "YTL")
      )
      (libsource (lib "*") (part "RESISTOR_Dup1"))
    )
    (comp (ref "R5533")
      (value "*")
      (footprint "R0402")
      (description "НЁУГєсД¤µзЧи,47K,+/-5%,R0402,1/16W.")
      (fields
        (field (name "PCB FOOTPRINT") "R0402")
        (field (name "TOLERANCE") "5%")
        (field (name "MANUFACTURER") "YAGEO")
        (field (name "ALTIUM_UNNAMED_1") "47K")
        (field (name "CREATED BY") "YTL")
      )
      (libsource (lib "*") (part "RESISTOR_Dup1"))
    )
    (comp (ref "R5534")
      (value "*")
      (footprint "R0402")
      (description "НЁУГєсД¤µзЧи,100K,+/-5%,R0402,1/16W.")
      (fields
        (field (name "PCB FOOTPRINT") "R0402")
        (field (name "TOLERANCE") "5%")
        (field (name "MANUFACTURER") "YAGEO")
        (field (name "ALTIUM_UNNAMED_1") "100K")
        (field (name "CREATED BY") "YTL")
      )
      (libsource (lib "*") (part "RESISTOR_Dup1"))
    )
    (comp (ref "R5535")
      (value "*")
      (footprint "R0402")
      (description "НЁУГєсД¤µзЧи,100K,+/-5%,R0402,1/16W.")
      (fields
        (field (name "PCB FOOTPRINT") "R0402")
        (field (name "TOLERANCE") "5%")
        (field (name "MANUFACTURER") "YAGEO")
        (field (name "ALTIUM_UNNAMED_1") "100K")
        (field (name "CREATED BY") "YTL")
      )
      (libsource (lib "*") (part "RESISTOR_Dup1"))
    )
    (comp (ref "R5536")
      (value "*")
      (footprint "R0402")
      (description "НЁУГєсД¤µзЧи,100K,+/-5%,R0402,1/16W.")
      (fields
        (field (name "PCB FOOTPRINT") "R0402")
        (field (name "TOLERANCE") "5%")
        (field (name "MANUFACTURER") "YAGEO")
        (field (name "ALTIUM_UNNAMED_1") "100K")
        (field (name "CREATED BY") "YTL")
      )
      (libsource (lib "*") (part "RESISTOR_Dup1"))
    )
    (comp (ref "R5537")
      (value "*")
      (footprint "R0402")
      (description "НЁУГєсД¤µзЧи,100K,+/-5%,R0402,1/16W.")
      (fields
        (field (name "PCB FOOTPRINT") "R0402")
        (field (name "TOLERANCE") "5%")
        (field (name "MANUFACTURER") "YAGEO")
        (field (name "ALTIUM_UNNAMED_1") "100K")
        (field (name "CREATED BY") "YTL")
      )
      (libsource (lib "*") (part "RESISTOR_Dup1"))
    )
    (comp (ref "R5538")
      (value "*")
      (footprint "R0402")
      (description "НЁУГєсД¤µзЧи,33R,+/-5%,R0402,1/16W.")
      (fields
        (field (name "PCB FOOTPRINT") "R0402")
        (field (name "TOLERANCE") "5%")
        (field (name "MANUFACTURER") "YAGEO")
        (field (name "ALTIUM_UNNAMED_1") "33R")
        (field (name "CREATED BY") "YTL")
      )
      (libsource (lib "*") (part "RESISTOR_Dup1"))
    )
    (comp (ref "R5539")
      (value "*")
      (footprint "R0402")
      (description "НЁУГєсД¤µзЧи,100K,+/-5%,R0402,1/16W.")
      (fields
        (field (name "PCB FOOTPRINT") "R0402")
        (field (name "TOLERANCE") "5%")
        (field (name "MANUFACTURER") "YAGEO")
        (field (name "ALTIUM_UNNAMED_1") "100K")
        (field (name "CREATED BY") "YTL")
      )
      (libsource (lib "*") (part "RESISTOR_Dup1"))
    )
    (comp (ref "R5540")
      (value "*")
      (footprint "R0402")
      (description "НЁУГєсД¤µзЧи,0R,+/-5%,R0402,1/16W.")
      (fields
        (field (name "PCB FOOTPRINT") "R0402")
        (field (name "TOLERANCE") "5%")
        (field (name "MANUFACTURER") "YAGEO")
        (field (name "OPTION") "DNP")
        (field (name "ALTIUM_UNNAMED_1") "0R")
        (field (name "CREATED BY") "YTL")
      )
      (libsource (lib "*") (part "RESISTOR_Dup1"))
    )
    (comp (ref "R5541")
      (value "*")
      (footprint "R0402")
      (description "НЁУГєсД¤µзЧи,100K,+/-5%,R0402,1/16W.")
      (fields
        (field (name "PCB FOOTPRINT") "R0402")
        (field (name "TOLERANCE") "5%")
        (field (name "MANUFACTURER") "YAGEO")
        (field (name "ALTIUM_UNNAMED_1") "100K")
        (field (name "CREATED BY") "YTL")
      )
      (libsource (lib "*") (part "RESISTOR_Dup1"))
    )
    (comp (ref "R5542")
      (value "*")
      (footprint "R0402")
      (description "НЁУГєсД¤µзЧи,10K,+/-5%,R0402,1/16W.")
      (fields
        (field (name "PCB FOOTPRINT") "R0402")
        (field (name "TOLERANCE") "5%")
        (field (name "MANUFACTURER") "YAGEO")
        (field (name "OPTION") "DNP")
        (field (name "ALTIUM_UNNAMED_1") "10K")
        (field (name "CREATED BY") "YTL")
      )
      (libsource (lib "*") (part "RESISTOR_Dup1"))
    )
    (comp (ref "R5543")
      (value "*")
      (footprint "R0402")
      (description "НЁУГєсД¤µзЧи,1K8,+/-5%,R0402,1/16W.")
      (fields
        (field (name "PCB FOOTPRINT") "R0402")
        (field (name "TOLERANCE") "5%")
        (field (name "MANUFACTURER") "YAGEO")
        (field (name "ALTIUM_UNNAMED_1") "1.8K")
        (field (name "CREATED BY") "YTL")
      )
      (libsource (lib "*") (part "RESISTOR_Dup1"))
    )
    (comp (ref "R5544")
      (value "*")
      (footprint "R0402")
      (description "НЁУГєсД¤µзЧи,22R,+/-5%,R0402,1/16W.")
      (fields
        (field (name "PCB FOOTPRINT") "R0402")
        (field (name "TOLERANCE") "5%")
        (field (name "MANUFACTURER") "YAGEO")
        (field (name "ALTIUM_UNNAMED_1") "22R")
        (field (name "CREATED BY") "YTL")
      )
      (libsource (lib "*") (part "RESISTOR_Dup1"))
    )
    (comp (ref "R5545")
      (value "*")
      (footprint "R0402")
      (description "НЁУГєсД¤µзЧи,100K,+/-5%,R0402,1/16W.")
      (fields
        (field (name "PCB FOOTPRINT") "R0402")
        (field (name "TOLERANCE") "5%")
        (field (name "MANUFACTURER") "YAGEO")
        (field (name "ALTIUM_UNNAMED_1") "100K")
        (field (name "CREATED BY") "YTL")
      )
      (libsource (lib "*") (part "RESISTOR_Dup1"))
    )
    (comp (ref "R5546")
      (value "*")
      (footprint "R0402")
      (description "НЁУГєсД¤µзЧи,10K,+/-5%,R0402,1/16W.")
      (fields
        (field (name "PCB FOOTPRINT") "R0402")
        (field (name "TOLERANCE") "5%")
        (field (name "MANUFACTURER") "YAGEO")
        (field (name "ALTIUM_UNNAMED_1") "10K")
        (field (name "CREATED BY") "YTL")
      )
      (libsource (lib "*") (part "RESISTOR_Dup1"))
    )
    (comp (ref "R5547")
      (value "*")
      (footprint "R0402")
      (description "НЁУГєсД¤µзЧи,10K,+/-5%,R0402,1/16W.")
      (fields
        (field (name "PCB FOOTPRINT") "R0402")
        (field (name "TOLERANCE") "5%")
        (field (name "MANUFACTURER") "YAGEO")
        (field (name "OPTION") "DNP")
        (field (name "ALTIUM_UNNAMED_1") "10K")
        (field (name "CREATED BY") "YTL")
      )
      (libsource (lib "*") (part "RESISTOR_Dup1"))
    )
    (comp (ref "R5548")
      (value "*")
      (footprint "R0402")
      (description "НЁУГєсД¤µзЧи,1K8,+/-5%,R0402,1/16W.")
      (fields
        (field (name "PCB FOOTPRINT") "R0402")
        (field (name "TOLERANCE") "5%")
        (field (name "MANUFACTURER") "YAGEO")
        (field (name "ALTIUM_UNNAMED_1") "1.8K")
        (field (name "CREATED BY") "YTL")
      )
      (libsource (lib "*") (part "RESISTOR_Dup1"))
    )
    (comp (ref "R5549")
      (value "*")
      (footprint "R0402")
      (description "НЁУГєсД¤µзЧи,10K,+/-5%,R0402,1/16W.")
      (fields
        (field (name "PCB FOOTPRINT") "R0402")
        (field (name "TOLERANCE") "5%")
        (field (name "MANUFACTURER") "YAGEO")
        (field (name "ALTIUM_UNNAMED_1") "10K")
        (field (name "CREATED BY") "YTL")
      )
      (libsource (lib "*") (part "RESISTOR_Dup1"))
    )
    (comp (ref "R5550")
      (value "*")
      (footprint "R0402")
      (description "НЁУГєсД¤µзЧи,22R,+/-5%,R0402,1/16W.")
      (fields
        (field (name "PCB FOOTPRINT") "R0402")
        (field (name "TOLERANCE") "5%")
        (field (name "MANUFACTURER") "YAGEO")
        (field (name "ALTIUM_UNNAMED_1") "22R")
        (field (name "CREATED BY") "YTL")
      )
      (libsource (lib "*") (part "RESISTOR_Dup1"))
    )
    (comp (ref "R5551")
      (value "*")
      (footprint "R0402")
      (description "НЁУГєсД¤µзЧи,51K,+/-5%,R0402,1/16W.")
      (fields
        (field (name "PCB FOOTPRINT") "R0402")
        (field (name "TOLERANCE") "5%")
        (field (name "MANUFACTURER") "YAGEO")
        (field (name "ALTIUM_UNNAMED_1") "51K")
        (field (name "CREATED BY") "YTL")
      )
      (libsource (lib "*") (part "RESISTOR_Dup1"))
    )
    (comp (ref "R5552")
      (value "*")
      (footprint "R0402")
      (description "НЁУГєсД¤µзЧи,10K,+/-5%,R0402,1/16W.")
      (fields
        (field (name "PCB FOOTPRINT") "R0402")
        (field (name "TOLERANCE") "5%")
        (field (name "MANUFACTURER") "YAGEO")
        (field (name "ALTIUM_UNNAMED_1") "10K")
        (field (name "CREATED BY") "YTL")
      )
      (libsource (lib "*") (part "RESISTOR_Dup1"))
    )
    (comp (ref "R5553")
      (value "*")
      (footprint "R0402")
      (description "НЁУГєсД¤µзЧи,100K,+/-1%,R0402,1/16W.")
      (fields
        (field (name "PCB FOOTPRINT") "R0402")
        (field (name "TOLERANCE") "1%")
        (field (name "MANUFACTURER") "YAGEO")
        (field (name "ALTIUM_UNNAMED_1") "100K")
        (field (name "CREATED BY") "YTL")
      )
      (libsource (lib "*") (part "RESISTOR_Dup1"))
    )
    (comp (ref "R5554")
      (value "*")
      (footprint "R0402")
      (description "НЁУГєсД¤µзЧи,100K,+/-1%,R0402,1/16W.")
      (fields
        (field (name "PCB FOOTPRINT") "R0402")
        (field (name "TOLERANCE") "1%")
        (field (name "MANUFACTURER") "YAGEO")
        (field (name "ALTIUM_UNNAMED_1") "100K")
        (field (name "CREATED BY") "YTL")
      )
      (libsource (lib "*") (part "RESISTOR_Dup1"))
    )
    (comp (ref "R5556")
      (value "*")
      (footprint "R0402")
      (description "НЁУГєсД¤µзЧи,10K,+/-5%,R0402,1/16W.")
      (fields
        (field (name "PCB FOOTPRINT") "R0402")
        (field (name "TOLERANCE") "5%")
        (field (name "OPTION") "DNP")
        (field (name "MANUFACTURER") "YAGEO")
        (field (name "ALTIUM_UNNAMED_1") "10K")
        (field (name "CREATED BY") "YTL")
      )
      (libsource (lib "*") (part "RESISTOR_Dup1"))
    )
    (comp (ref "TP5500")
      (value "*")
      (footprint "TEST")
      (description "Test Point 0.7mm")
      (fields (field (name "ALTIUM_UNNAMED_1") "TP_0.7") (field (name "CREATED BY") "JJJ"))
      (libsource (lib "*") (part "TP"))
    )
    (comp (ref "U5500")
      (value "*")
      (footprint "QFN56")
      (fields
        (field (name "PCB FOOTPRINT") "QFN56_8R00X8R00X0R90_T")
        (field (name "ALTIUM_UNNAMED_1") "IT6161")
      )
      (libsource (lib "*") (part "IT6161"))
    )
    (comp (ref "U5501")
      (value "*")
      (footprint "SOT_23_5")
      (description "High Efficiency 5.5V, 2A continuous, 3A peak, 1MHz Synchronous Step Down Regulator")
      (fields
        (field (name "PCB FOOTPRINT") "SOT_23_5")
        (field (name "MANUFACTURER") "SilergyЈЁОщБ¦ЅЬЈ©")
        (field (name "ALTIUM_UNNAMED_1") "ETA3409/SY8089AAC")
        (field (name "CREATED BY") "JJJ")
      )
      (libsource (lib "*") (part "DCDC_SY8088"))
    )
  )
  (nets
    (net (code "1") (name "/CKDN") (class "Default")
      (node (ref "R5525") (pin "2") (pinfunction "2_2") (pintype "passive"))
      (node (ref "U5500") (pin "8") (pinfunction "CKDN_8") (pintype "passive"))
    )
    (net (code "2") (name "/CKDP") (class "Default")
      (node (ref "R5526") (pin "2") (pinfunction "2_2") (pintype "passive"))
      (node (ref "U5500") (pin "9") (pinfunction "CKDP_9") (pintype "passive"))
    )
    (net (code "3") (name "/ENTEST") (class "Default")
      (node (ref "R5513") (pin "1") (pinfunction "1_1") (pintype "passive"))
      (node (ref "U5500") (pin "44") (pinfunction "ENTEST_44") (pintype "passive"))
    )
    (net (code "4") (name "/HDMI3_TX0N") (class "Default")
      (node (ref "R5518") (pin "1") (pinfunction "1_1") (pintype "passive"))
      (node (ref "U5500") (pin "35") (pinfunction "TX0M_35") (pintype "passive"))
    )
    (net (code "5") (name "/HDMI3_TX0N_PORT") (class "Default")
      (node (ref "ED5501") (pin "2") (pinfunction "IO2_2") (pintype "passive"))
      (node (ref "ED5501") (pin "9") (pinfunction "NC_9_9") (pintype "passive"))
      (node (ref "J5500") (pin "9") (pinfunction "D0N_9") (pintype "passive"))
      (node (ref "R5518") (pin "2") (pinfunction "2_2") (pintype "passive"))
    )
    (net (code "6") (name "/HDMI3_TX0P") (class "Default")
      (node (ref "R5517") (pin "1") (pinfunction "1_1") (pintype "passive"))
      (node (ref "U5500") (pin "36") (pinfunction "TX0P_36") (pintype "passive"))
    )
    (net (code "7") (name "/HDMI3_TX0P_PORT") (class "Default")
      (node (ref "ED5501") (pin "1") (pinfunction "IO1_1") (pintype "passive"))
      (node (ref "ED5501") (pin "10") (pinfunction "NC_10_10") (pintype "passive"))
      (node (ref "J5500") (pin "7") (pinfunction "D0P_7") (pintype "passive"))
      (node (ref "R5517") (pin "2") (pinfunction "2_2") (pintype "passive"))
    )
    (net (code "8") (name "/HDMI3_TX1N") (class "Default")
      (node (ref "R5512") (pin "1") (pinfunction "1_1") (pintype "passive"))
      (node (ref "U5500") (pin "37") (pinfunction "TX1M_37") (pintype "passive"))
    )
    (net (code "9") (name "/HDMI3_TX1N_PORT") (class "Default")
      (node (ref "ED5500") (pin "5") (pinfunction "IO4_5") (pintype "passive"))
      (node (ref "ED5500") (pin "6") (pinfunction "NC_6_6") (pintype "passive"))
      (node (ref "J5500") (pin "6") (pinfunction "D1N_6") (pintype "passive"))
      (node (ref "R5512") (pin "2") (pinfunction "2_2") (pintype "passive"))
    )
    (net (code "10") (name "/HDMI3_TX1P") (class "Default")
      (node (ref "R5515") (pin "1") (pinfunction "1_1") (pintype "passive"))
      (node (ref "U5500") (pin "38") (pinfunction "TX1P_38") (pintype "passive"))
    )
    (net (code "11") (name "/HDMI3_TX1P_PORT") (class "Default")
      (node (ref "ED5500") (pin "4") (pinfunction "IO3_4") (pintype "passive"))
      (node (ref "ED5500") (pin "7") (pinfunction "NC_7_7") (pintype "passive"))
      (node (ref "J5500") (pin "4") (pinfunction "D1P_4") (pintype "passive"))
      (node (ref "R5515") (pin "2") (pinfunction "2_2") (pintype "passive"))
    )
    (net (code "12") (name "/HDMI3_TX2N") (class "Default")
      (node (ref "R5516") (pin "1") (pinfunction "1_1") (pintype "passive"))
      (node (ref "U5500") (pin "40") (pinfunction "TX2M_40") (pintype "passive"))
    )
    (net (code "13") (name "/HDMI3_TX2N_PORT") (class "Default")
      (node (ref "ED5500") (pin "2") (pinfunction "IO2_2") (pintype "passive"))
      (node (ref "ED5500") (pin "9") (pinfunction "NC_9_9") (pintype "passive"))
      (node (ref "J5500") (pin "3") (pinfunction "D2N_3") (pintype "passive"))
      (node (ref "R5516") (pin "2") (pinfunction "2_2") (pintype "passive"))
    )
    (net (code "14") (name "/HDMI3_TX2P") (class "Default")
      (node (ref "R5514") (pin "1") (pinfunction "1_1") (pintype "passive"))
      (node (ref "U5500") (pin "41") (pinfunction "TX2P_41") (pintype "passive"))
    )
    (net (code "15") (name "/HDMI3_TX2P_PORT") (class "Default")
      (node (ref "ED5500") (pin "1") (pinfunction "IO1_1") (pintype "passive"))
      (node (ref "ED5500") (pin "10") (pinfunction "NC_10_10") (pintype "passive"))
      (node (ref "J5500") (pin "1") (pinfunction "D2P_1") (pintype "passive"))
      (node (ref "R5514") (pin "2") (pinfunction "2_2") (pintype "passive"))
    )
    (net (code "16") (name "/HDMI3_TXCN") (class "Default")
      (node (ref "C5501") (pin "2") (pinfunction "2_2") (pintype "passive"))
      (node (ref "L5500") (pin "4") (pinfunction "4_4") (pintype "passive"))
      (node (ref "R5522") (pin "1") (pinfunction "1_1") (pintype "passive"))
      (node (ref "U5500") (pin "32") (pinfunction "TXCM_32") (pintype "passive"))
    )
    (net (code "17") (name "/HDMI3_TXCN_PORT") (class "Default")
      (node (ref "ED5501") (pin "5") (pinfunction "IO4_5") (pintype "passive"))
      (node (ref "ED5501") (pin "6") (pinfunction "NC_6_6") (pintype "passive"))
      (node (ref "J5500") (pin "12") (pinfunction "CLKN_12") (pintype "passive"))
      (node (ref "L5500") (pin "3") (pinfunction "3_3") (pintype "passive"))
      (node (ref "R5522") (pin "2") (pinfunction "2_2") (pintype "passive"))
    )
    (net (code "18") (name "/HDMI3_TXCP") (class "Default")
      (node (ref "C5501") (pin "1") (pinfunction "1_1") (pintype "passive"))
      (node (ref "L5500") (pin "2") (pinfunction "2_2") (pintype "passive"))
      (node (ref "R5519") (pin "1") (pinfunction "1_1") (pintype "passive"))
      (node (ref "U5500") (pin "33") (pinfunction "TXCP_33") (pintype "passive"))
    )
    (net (code "19") (name "/HDMI3_TXCP_PORT") (class "Default")
      (node (ref "ED5501") (pin "4") (pinfunction "IO3_4") (pintype "passive"))
      (node (ref "ED5501") (pin "7") (pinfunction "NC_7_7") (pintype "passive"))
      (node (ref "J5500") (pin "10") (pinfunction "CLKP_10") (pintype "passive"))
      (node (ref "L5500") (pin "1") (pinfunction "1_1") (pintype "passive"))
      (node (ref "R5519") (pin "2") (pinfunction "2_2") (pintype "passive"))
    )
    (net (code "20") (name "/HDMI3_TX_CEC") (class "Default")
      (node (ref "ED5505") (pin "1") (pinfunction "1_1") (pintype "passive"))
      (node (ref "J5500") (pin "13") (pinfunction "CEC_13") (pintype "passive"))
      (node (ref "R5538") (pin "2") (pinfunction "2_2") (pintype "passive"))
    )
    (net (code "21") (name "/HDMI3_TX_HPD") (class "Default")
      (node (ref "R5528") (pin "1") (pinfunction "1_1") (pintype "passive"))
      (node (ref "U5500") (pin "23") (pinfunction "HPD_23") (pintype "passive"))
    )
    (net (code "22") (name "/HDMI3_TX_HPD_PORT") (class "Default")
      (node (ref "ED5502") (pin "1") (pinfunction "1_1") (pintype "passive"))
      (node (ref "J5500") (pin "19") (pinfunction "HPD_19") (pintype "passive"))
      (node (ref "R5528") (pin "2") (pinfunction "2_2") (pintype "passive"))
      (node (ref "R5533") (pin "1") (pinfunction "1_1") (pintype "passive"))
    )
    (net (code "23") (name "/HDMI3_TX_SCL") (class "Default")
      (node (ref "Q5501") (pin "2") (pinfunction "SOURCE_2") (pintype "passive"))
      (node (ref "R5542") (pin "2") (pinfunction "2_2") (pintype "passive"))
      (node (ref "R5544") (pin "1") (pinfunction "1_1") (pintype "passive"))
      (node (ref "U5500") (pin "25") (pinfunction "DDCSCL_25") (pintype "passive"))
    )
    (net (code "24") (name "/HDMI3_TX_SCL_PORT") (class "Default")
      (node (ref "ED5504") (pin "1") (pinfunction "1_1") (pintype "passive"))
      (node (ref "J5500") (pin "15") (pinfunction "SCL_15") (pintype "passive"))
      (node (ref "Q5501") (pin "3") (pinfunction "DRAIN_3") (pintype "passive"))
      (node (ref "R5543") (pin "2") (pinfunction "2_2") (pintype "passive"))
      (node (ref "R5544") (pin "2") (pinfunction "2_2") (pintype "passive"))
    )
    (net (code "25") (name "/HDMI3_TX_SDA") (class "Default")
      (node (ref "Q5502") (pin "2") (pinfunction "SOURCE_2") (pintype "passive"))
      (node (ref "R5547") (pin "2") (pinfunction "2_2") (pintype "passive"))
      (node (ref "R5550") (pin "1") (pinfunction "1_1") (pintype "passive"))
      (node (ref "U5500") (pin "24") (pinfunction "DDCSDA_24") (pintype "passive"))
    )
    (net (code "26") (name "/HDMI3_TX_SDA_PORT") (class "Default")
      (node (ref "ED5503") (pin "1") (pinfunction "1_1") (pintype "passive"))
      (node (ref "J5500") (pin "16") (pinfunction "SDA_16") (pintype "passive"))
      (node (ref "Q5502") (pin "3") (pinfunction "DRAIN_3") (pintype "passive"))
      (node (ref "R5548") (pin "2") (pinfunction "2_2") (pintype "passive"))
      (node (ref "R5550") (pin "2") (pinfunction "2_2") (pintype "passive"))
    )
    (net (code "27") (name "/IT6161SYSRSTN") (class "Default")
      (node (ref "C5500") (pin "1") (pinfunction "1_1") (pintype "passive"))
      (node (ref "R5503") (pin "1") (pinfunction "1_1") (pintype "passive"))
      (node (ref "R5504") (pin "1") (pinfunction "1_1") (pintype "passive"))
      (node (ref "U5500") (pin "46") (pinfunction "SYSRTN_46") (pintype "passive"))
    )
    (net (code "28") (name "/IT6161_INT") (class "Default")
      (node (ref "R5500") (pin "1") (pinfunction "1_1") (pintype "passive"))
      (node (ref "U5500") (pin "49") (pinfunction "INT_49") (pintype "passive"))
    )
    (net (code "29") (name "/IT6161_PCSCL") (class "Default")
      (node (ref "R5502") (pin "1") (pinfunction "1_1") (pintype "passive"))
      (node (ref "U5500") (pin "47") (pinfunction "PCSCL_47") (pintype "passive"))
    )
    (net (code "30") (name "/IT6161_PCSDA") (class "Default")
      (node (ref "R5501") (pin "1") (pinfunction "1_1") (pintype "passive"))
      (node (ref "U5500") (pin "48") (pinfunction "PCSDA_48") (pintype "passive"))
    )
    (net (code "31") (name "/L0DN") (class "Default")
      (node (ref "R5530") (pin "2") (pinfunction "2_2") (pintype "passive"))
      (node (ref "U5500") (pin "12") (pinfunction "L0DN_12") (pintype "passive"))
    )
    (net (code "32") (name "/L0DP") (class "Default")
      (node (ref "R5532") (pin "2") (pinfunction "2_2") (pintype "passive"))
      (node (ref "U5500") (pin "13") (pinfunction "L0DP_13") (pintype "passive"))
    )
    (net (code "33") (name "/L1DN") (class "Default")
      (node (ref "R5527") (pin "2") (pinfunction "2_2") (pintype "passive"))
      (node (ref "U5500") (pin "10") (pinfunction "L1DN_10") (pintype "passive"))
    )
    (net (code "34") (name "/L1DP") (class "Default")
      (node (ref "R5529") (pin "2") (pinfunction "2_2") (pintype "passive"))
      (node (ref "U5500") (pin "11") (pinfunction "L1DP_11") (pintype "passive"))
    )
    (net (code "35") (name "/L2DN") (class "Default")
      (node (ref "R5523") (pin "2") (pinfunction "2_2") (pintype "passive"))
      (node (ref "U5500") (pin "6") (pinfunction "L2DN_6") (pintype "passive"))
    )
    (net (code "36") (name "/L2DP") (class "Default")
      (node (ref "R5524") (pin "2") (pinfunction "2_2") (pintype "passive"))
      (node (ref "U5500") (pin "7") (pinfunction "L2DP_7") (pintype "passive"))
    )
    (net (code "37") (name "/L3DN") (class "Default")
      (node (ref "R5520") (pin "2") (pinfunction "2_2") (pintype "passive"))
      (node (ref "U5500") (pin "4") (pinfunction "L3DN_4") (pintype "passive"))
    )
    (net (code "38") (name "/L3DP") (class "Default")
      (node (ref "R5521") (pin "2") (pinfunction "2_2") (pintype "passive"))
      (node (ref "U5500") (pin "5") (pinfunction "L3DP_5") (pintype "passive"))
    )
    (net (code "39") (name "/PCADR") (class "Default")
      (node (ref "R5507") (pin "1") (pinfunction "1_1") (pintype "passive"))
      (node (ref "R5509") (pin "1") (pinfunction "1_1") (pintype "passive"))
      (node (ref "U5500") (pin "45") (pinfunction "PCADR_45") (pintype "passive"))
    )
    (net (code "40") (name "DP2HDMI_PWREN_H_GPIO3_B2") (class "Default")
      (node (ref "R5549") (pin "1") (pinfunction "1_1") (pintype "passive"))
      (node (ref "R5552") (pin "1") (pinfunction "1_1") (pintype "passive"))
    )
    (net (code "41") (name "GND") (class "Default")
      (node (ref "C5500") (pin "2") (pinfunction "2_2") (pintype "passive"))
      (node (ref "C5502") (pin "2") (pinfunction "2_2") (pintype "passive"))
      (node (ref "C5503") (pin "2") (pinfunction "2_2") (pintype "passive"))
      (node (ref "C5505") (pin "2") (pinfunction "2_2") (pintype "passive"))
      (node (ref "C5506") (pin "2") (pinfunction "2_2") (pintype "passive"))
      (node (ref "C5507") (pin "2") (pinfunction "2_2") (pintype "passive"))
      (node (ref "C5508") (pin "2") (pinfunction "2_2") (pintype "passive"))
      (node (ref "C5509") (pin "2") (pinfunction "2_2") (pintype "passive"))
      (node (ref "C5510") (pin "2") (pinfunction "2_2") (pintype "passive"))
      (node (ref "C5511") (pin "2") (pinfunction "2_2") (pintype "passive"))
      (node (ref "C5512") (pin "2") (pinfunction "2_2") (pintype "passive"))
      (node (ref "C5513") (pin "2") (pinfunction "2_2") (pintype "passive"))
      (node (ref "C5514") (pin "2") (pinfunction "2_2") (pintype "passive"))
      (node (ref "C5516") (pin "2") (pinfunction "2_2") (pintype "passive"))
      (node (ref "C5517") (pin "2") (pinfunction "2_2") (pintype "passive"))
      (node (ref "C5518") (pin "2") (pinfunction "2_2") (pintype "passive"))
      (node (ref "C5519") (pin "2") (pinfunction "2_2") (pintype "passive"))
      (node (ref "C5520") (pin "2") (pinfunction "2_2") (pintype "passive"))
      (node (ref "C5521") (pin "2") (pinfunction "2_2") (pintype "passive"))
      (node (ref "C5522") (pin "2") (pinfunction "2_2") (pintype "passive"))
      (node (ref "C5523") (pin "2") (pinfunction "2_2") (pintype "passive"))
      (node (ref "C5524") (pin "2") (pinfunction "2_2") (pintype "passive"))
      (node (ref "C5525") (pin "2") (pinfunction "2_2") (pintype "passive"))
      (node (ref "C5526") (pin "2") (pinfunction "2_2") (pintype "passive"))
      (node (ref "C5527") (pin "2") (pinfunction "2_2") (pintype "passive"))
      (node (ref "C5528") (pin "2") (pinfunction "2_2") (pintype "passive"))
      (node (ref "C5529") (pin "2") (pinfunction "2_2") (pintype "passive"))
      (node (ref "C5530") (pin "2") (pinfunction "2_2") (pintype "passive"))
      (node (ref "C5531") (pin "2") (pinfunction "2_2") (pintype "passive"))
      (node (ref "C5532") (pin "2") (pinfunction "2_2") (pintype "passive"))
      (node (ref "C5533") (pin "2") (pinfunction "2_2") (pintype "passive"))
      (node (ref "ED5500") (pin "3") (pinfunction "GND_3") (pintype "power_in"))
      (node (ref "ED5500") (pin "8") (pinfunction "GND_8") (pintype "power_in"))
      (node (ref "ED5501") (pin "3") (pinfunction "GND_3") (pintype "power_in"))
      (node (ref "ED5501") (pin "8") (pinfunction "GND_8") (pintype "power_in"))
      (node (ref "ED5502") (pin "2") (pinfunction "2_2") (pintype "passive"))
      (node (ref "ED5503") (pin "2") (pinfunction "2_2") (pintype "passive"))
      (node (ref "ED5504") (pin "2") (pinfunction "2_2") (pintype "passive"))
      (node (ref "ED5505") (pin "2") (pinfunction "2_2") (pintype "passive"))
      (node (ref "J5500") (pin "11") (pinfunction "CLK_G_11") (pintype "passive"))
      (node (ref "J5500") (pin "17") (pinfunction "GND_17") (pintype "passive"))
      (node (ref "J5500") (pin "2") (pinfunction "D2_G_2") (pintype "passive"))
      (node (ref "J5500") (pin "20") (pinfunction "G1_20") (pintype "passive"))
      (node (ref "J5500") (pin "21") (pinfunction "G2_21") (pintype "passive"))
      (node (ref "J5500") (pin "22") (pinfunction "G3_22") (pintype "passive"))
      (node (ref "J5500") (pin "23") (pinfunction "G4_23") (pintype "passive"))
      (node (ref "J5500") (pin "5") (pinfunction "D1_G_5") (pintype "passive"))
      (node (ref "J5500") (pin "8") (pinfunction "D0_G_8") (pintype "passive"))
      (node (ref "Q5503") (pin "2") (pinfunction "EMITTER_2") (pintype "passive"))
      (node (ref "R5506") (pin "2") (pinfunction "2_2") (pintype "passive"))
      (node (ref "R5507") (pin "2") (pinfunction "2_2") (pintype "passive"))
      (node (ref "R5508") (pin "2") (pinfunction "2_2") (pintype "passive"))
      (node (ref "R5510") (pin "2") (pinfunction "2_2") (pintype "passive"))
      (node (ref "R5511") (pin "2") (pinfunction "2_2") (pintype "passive"))
      (node (ref "R5513") (pin "2") (pinfunction "2_2") (pintype "passive"))
      (node (ref "R5531") (pin "2") (pinfunction "2_2") (pintype "passive"))
      (node (ref "R5533") (pin "2") (pinfunction "2_2") (pintype "passive"))
      (node (ref "R5534") (pin "2") (pinfunction "2_2") (pintype "passive"))
      (node (ref "R5535") (pin "2") (pinfunction "2_2") (pintype "passive"))
      (node (ref "R5536") (pin "2") (pinfunction "2_2") (pintype "passive"))
      (node (ref "R5537") (pin "2") (pinfunction "2_2") (pintype "passive"))
      (node (ref "R5539") (pin "2") (pinfunction "2_2") (pintype "passive"))
      (node (ref "R5541") (pin "2") (pinfunction "2_2") (pintype "passive"))
      (node (ref "R5551") (pin "2") (pinfunction "2_2") (pintype "passive"))
      (node (ref "R5554") (pin "2") (pinfunction "2_2") (pintype "passive"))
      (node (ref "U5500") (pin "57") (pinfunction "EPAD_57") (pintype "passive"))
      (node (ref "U5501") (pin "2") (pinfunction "GND_2") (pintype "passive"))
    )
    (net (code "42") (name "I2C6_SCL_M0") (class "Default")
      (node (ref "R5502") (pin "2") (pinfunction "2_2") (pintype "passive"))
    )
    (net (code "43") (name "I2C6_SDA_M0") (class "Default")
      (node (ref "R5501") (pin "2") (pinfunction "2_2") (pintype "passive"))
    )
    (net (code "44") (name "IT6161_INT_GPIO0_C4") (class "Default")
      (node (ref "R5500") (pin "2") (pinfunction "2_2") (pintype "passive"))
    )
    (net (code "45") (name "IT6161_SYSRSTN_GPIO0_C5") (class "Default")
      (node (ref "R5503") (pin "2") (pinfunction "2_2") (pintype "passive"))
    )
    (net (code "46") (name "MIPI_DPHY1_TX_CLKN") (class "Default")
      (node (ref "R5525") (pin "1") (pinfunction "1_1") (pintype "passive"))
    )
    (net (code "47") (name "MIPI_DPHY1_TX_CLKP") (class "Default")
      (node (ref "R5526") (pin "1") (pinfunction "1_1") (pintype "passive"))
    )
    (net (code "48") (name "MIPI_DPHY1_TX_D0N") (class "Default")
      (node (ref "R5530") (pin "1") (pinfunction "1_1") (pintype "passive"))
    )
    (net (code "49") (name "MIPI_DPHY1_TX_D0P") (class "Default")
      (node (ref "R5532") (pin "1") (pinfunction "1_1") (pintype "passive"))
    )
    (net (code "50") (name "MIPI_DPHY1_TX_D1N") (class "Default")
      (node (ref "R5527") (pin "1") (pinfunction "1_1") (pintype "passive"))
    )
    (net (code "51") (name "MIPI_DPHY1_TX_D1P") (class "Default")
      (node (ref "R5529") (pin "1") (pinfunction "1_1") (pintype "passive"))
    )
    (net (code "52") (name "MIPI_DPHY1_TX_D2N") (class "Default")
      (node (ref "R5523") (pin "1") (pinfunction "1_1") (pintype "passive"))
    )
    (net (code "53") (name "MIPI_DPHY1_TX_D2P") (class "Default")
      (node (ref "R5524") (pin "1") (pinfunction "1_1") (pintype "passive"))
    )
    (net (code "54") (name "MIPI_DPHY1_TX_D3N") (class "Default")
      (node (ref "R5520") (pin "1") (pinfunction "1_1") (pintype "passive"))
    )
    (net (code "55") (name "MIPI_DPHY1_TX_D3P") (class "Default")
      (node (ref "R5521") (pin "1") (pinfunction "1_1") (pintype "passive"))
    )
    (net (code "56") (name "Net-(D5501-K)") (class "Default")
      (node (ref "D5501") (pin "2") (pinfunction "K_2") (pintype "passive"))
      (node (ref "R5543") (pin "1") (pinfunction "1_1") (pintype "passive"))
      (node (ref "R5548") (pin "1") (pinfunction "1_1") (pintype "passive"))
    )
    (net (code "57") (name "Net-(Q5500-GATE)") (class "Default")
      (node (ref "C5504") (pin "2") (pinfunction "2_2") (pintype "passive"))
      (node (ref "Q5500") (pin "1") (pinfunction "GATE_1") (pintype "passive"))
      (node (ref "R5545") (pin "2") (pinfunction "2_2") (pintype "passive"))
      (node (ref "R5546") (pin "1") (pinfunction "1_1") (pintype "passive"))
    )
    (net (code "58") (name "Net-(Q5503-BASE)") (class "Default")
      (node (ref "C5512") (pin "1") (pinfunction "1_1") (pintype "passive"))
      (node (ref "Q5503") (pin "1") (pinfunction "BASE_1") (pintype "passive"))
      (node (ref "R5549") (pin "2") (pinfunction "2_2") (pintype "passive"))
      (node (ref "R5551") (pin "1") (pinfunction "1_1") (pintype "passive"))
    )
    (net (code "59") (name "Net-(Q5503-COLLECTOR)") (class "Default")
      (node (ref "Q5503") (pin "3") (pinfunction "COLLECTOR_3") (pintype "passive"))
      (node (ref "R5546") (pin "2") (pinfunction "2_2") (pintype "passive"))
    )
    (net (code "60") (name "Net-(U5500-CEC)") (class "Default")
      (node (ref "R5538") (pin "1") (pinfunction "1_1") (pintype "passive"))
      (node (ref "U5500") (pin "26") (pinfunction "CEC_26") (pintype "passive"))
    )
    (net (code "61") (name "Net-(U5500-DSD3R)") (class "Default")
      (node (ref "R5510") (pin "1") (pinfunction "1_1") (pintype "passive"))
      (node (ref "U5500") (pin "55") (pinfunction "DSD3R_55") (pintype "passive"))
    )
    (net (code "62") (name "Net-(U5500-EXTPCLK)") (class "Default")
      (node (ref "TP5500") (pin "1") (pinfunction "1_1") (pintype "passive"))
      (node (ref "U5500") (pin "1") (pinfunction "EXTPCLK_1") (pintype "passive"))
    )
    (net (code "63") (name "Net-(U5500-I2S0)") (class "Default")
      (node (ref "R5537") (pin "1") (pinfunction "1_1") (pintype "passive"))
      (node (ref "U5500") (pin "18") (pinfunction "I2S0_18") (pintype "passive"))
    )
    (net (code "64") (name "Net-(U5500-I2S1)") (class "Default")
      (node (ref "R5536") (pin "1") (pinfunction "1_1") (pintype "passive"))
      (node (ref "U5500") (pin "17") (pinfunction "I2S1_17") (pintype "passive"))
    )
    (net (code "65") (name "Net-(U5500-I2S2)") (class "Default")
      (node (ref "R5535") (pin "1") (pinfunction "1_1") (pintype "passive"))
      (node (ref "U5500") (pin "16") (pinfunction "I2S2_16") (pintype "passive"))
    )
    (net (code "66") (name "Net-(U5500-I2S3)") (class "Default")
      (node (ref "R5534") (pin "1") (pinfunction "1_1") (pintype "passive"))
      (node (ref "U5500") (pin "15") (pinfunction "I2S3_15") (pintype "passive"))
    )
    (net (code "67") (name "Net-(U5500-MCLK)") (class "Default")
      (node (ref "R5508") (pin "1") (pinfunction "1_1") (pintype "passive"))
      (node (ref "U5500") (pin "54") (pinfunction "MCLK_54") (pintype "passive"))
    )
    (net (code "68") (name "Net-(U5500-REXT)") (class "Default")
      (node (ref "R5531") (pin "1") (pinfunction "1_1") (pintype "passive"))
      (node (ref "U5500") (pin "31") (pinfunction "REXT_31") (pintype "passive"))
    )
    (net (code "69") (name "Net-(U5500-SCK)") (class "Default")
      (node (ref "R5541") (pin "1") (pinfunction "1_1") (pintype "passive"))
      (node (ref "U5500") (pin "21") (pinfunction "SCK_21") (pintype "passive"))
    )
    (net (code "70") (name "Net-(U5500-STDBY)") (class "Default")
      (node (ref "R5511") (pin "1") (pinfunction "1_1") (pintype "passive"))
      (node (ref "R5556") (pin "1") (pinfunction "1_1") (pintype "passive"))
      (node (ref "U5500") (pin "56") (pinfunction "STDBY_56") (pintype "passive"))
    )
    (net (code "71") (name "Net-(U5500-WS)") (class "Default")
      (node (ref "R5539") (pin "1") (pinfunction "1_1") (pintype "passive"))
      (node (ref "U5500") (pin "20") (pinfunction "WS_20") (pintype "passive"))
    )
    (net (code "72") (name "Net-(U5501-EN)") (class "Default")
      (node (ref "C5531") (pin "1") (pinfunction "1_1") (pintype "passive"))
      (node (ref "R5552") (pin "2") (pinfunction "2_2") (pintype "passive"))
      (node (ref "U5501") (pin "1") (pinfunction "EN_1") (pintype "passive"))
    )
    (net (code "73") (name "Net-(U5501-FB{slash}OUT)") (class "Default")
      (node (ref "C5515") (pin "2") (pinfunction "2_2") (pintype "passive"))
      (node (ref "R5553") (pin "2") (pinfunction "2_2") (pintype "passive"))
      (node (ref "R5554") (pin "1") (pinfunction "1_1") (pintype "passive"))
      (node (ref "U5501") (pin "5") (pinfunction "FB/OUT_5") (pintype "passive"))
    )
    (net (code "74") (name "Net-(U5501-LX)") (class "Default")
      (node (ref "L5501") (pin "1") (pinfunction "1_1") (pintype "passive"))
      (node (ref "U5501") (pin "3") (pinfunction "LX_3") (pintype "passive"))
    )
    (net (code "75") (name "SPDIF0_TX_M1") (class "Default")
      (node (ref "R5506") (pin "1") (pinfunction "1_1") (pintype "passive"))
      (node (ref "U5500") (pin "53") (pinfunction "SPDIF_53") (pintype "passive"))
    )
    (net (code "76") (name "VCC4V0_SYS") (class "Default")
      (node (ref "C5520") (pin "1") (pinfunction "1_1") (pintype "passive"))
      (node (ref "U5501") (pin "4") (pinfunction "VIN_4") (pintype "passive"))
    )
    (net (code "77") (name "VCC5V0_SYS") (class "Default")
      (node (ref "D5500") (pin "1") (pinfunction "A_1") (pintype "passive"))
      (node (ref "D5501") (pin "1") (pinfunction "A_1") (pintype "passive"))
      (node (ref "R5540") (pin "1") (pinfunction "1_1") (pintype "passive"))
    )
    (net (code "78") (name "VCC5V_HDMI_TX3") (class "Default")
      (node (ref "C5502") (pin "1") (pinfunction "1_1") (pintype "passive"))
      (node (ref "D5500") (pin "2") (pinfunction "K_2") (pintype "passive"))
      (node (ref "J5500") (pin "18") (pinfunction "+5V_18") (pintype "passive"))
      (node (ref "R5540") (pin "2") (pinfunction "2_2") (pintype "passive"))
    )
    (net (code "79") (name "VCCA_PVCC33_6161") (class "Default")
      (node (ref "C5508") (pin "1") (pinfunction "1_1") (pintype "passive"))
      (node (ref "C5509") (pin "1") (pinfunction "1_1") (pintype "passive"))
      (node (ref "FB5500") (pin "2") (pinfunction "2_2") (pintype "passive"))
      (node (ref "U5500") (pin "30") (pinfunction "PVCC33_30_30") (pintype "passive"))
    )
    (net (code "80") (name "VCC_3V3") (class "Default")
      (node (ref "C5503") (pin "1") (pinfunction "1_1") (pintype "passive"))
      (node (ref "C5504") (pin "1") (pinfunction "1_1") (pintype "passive"))
      (node (ref "Q5500") (pin "2") (pinfunction "SOURCE_2") (pintype "passive"))
      (node (ref "R5545") (pin "1") (pinfunction "1_1") (pintype "passive"))
    )
    (net (code "81") (name "VCC_OVDD33_6161") (class "Default")
      (node (ref "C5505") (pin "1") (pinfunction "1_1") (pintype "passive"))
      (node (ref "C5506") (pin "1") (pinfunction "1_1") (pintype "passive"))
      (node (ref "C5507") (pin "1") (pinfunction "1_1") (pintype "passive"))
      (node (ref "C5510") (pin "1") (pinfunction "1_1") (pintype "passive"))
      (node (ref "C5511") (pin "1") (pinfunction "1_1") (pintype "passive"))
      (node (ref "FB5500") (pin "1") (pinfunction "1_1") (pintype "passive"))
      (node (ref "Q5500") (pin "3") (pinfunction "DRAIN_3") (pintype "passive"))
      (node (ref "Q5501") (pin "1") (pinfunction "GATE_1") (pintype "passive"))
      (node (ref "Q5502") (pin "1") (pinfunction "GATE_1") (pintype "passive"))
      (node (ref "R5504") (pin "2") (pinfunction "2_2") (pintype "passive"))
      (node (ref "R5509") (pin "2") (pinfunction "2_2") (pintype "passive"))
      (node (ref "R5542") (pin "1") (pinfunction "1_1") (pintype "passive"))
      (node (ref "R5547") (pin "1") (pinfunction "1_1") (pintype "passive"))
      (node (ref "R5556") (pin "2") (pinfunction "2_2") (pintype "passive"))
      (node (ref "U5500") (pin "19") (pinfunction "OVDD1833_19_19") (pintype "passive"))
      (node (ref "U5500") (pin "27") (pinfunction "OVDD33_27_27") (pintype "passive"))
      (node (ref "U5500") (pin "50") (pinfunction "OVDD1833_50_50") (pintype "passive"))
    )
    (net (code "82") (name "VDD_AVCC12_6161") (class "Default")
      (node (ref "C5513") (pin "1") (pinfunction "1_1") (pintype "passive"))
      (node (ref "C5514") (pin "1") (pinfunction "1_1") (pintype "passive"))
      (node (ref "FB5501") (pin "2") (pinfunction "2_2") (pintype "passive"))
      (node (ref "U5500") (pin "34") (pinfunction "AVCC12_34_34") (pintype "passive"))
    )
    (net (code "83") (name "VDD_IVDD12_6161") (class "Default")
      (node (ref "C5515") (pin "1") (pinfunction "1_1") (pintype "passive"))
      (node (ref "C5521") (pin "1") (pinfunction "1_1") (pintype "passive"))
      (node (ref "C5522") (pin "1") (pinfunction "1_1") (pintype "passive"))
      (node (ref "C5523") (pin "1") (pinfunction "1_1") (pintype "passive"))
      (node (ref "C5524") (pin "1") (pinfunction "1_1") (pintype "passive"))
      (node (ref "C5525") (pin "1") (pinfunction "1_1") (pintype "passive"))
      (node (ref "C5526") (pin "1") (pinfunction "1_1") (pintype "passive"))
      (node (ref "C5527") (pin "1") (pinfunction "1_1") (pintype "passive"))
      (node (ref "FB5501") (pin "1") (pinfunction "1_1") (pintype "passive"))
      (node (ref "FB5502") (pin "1") (pinfunction "1_1") (pintype "passive"))
      (node (ref "FB5503") (pin "1") (pinfunction "1_1") (pintype "passive"))
      (node (ref "FB5504") (pin "1") (pinfunction "1_1") (pintype "passive"))
      (node (ref "FB5505") (pin "1") (pinfunction "1_1") (pintype "passive"))
      (node (ref "L5501") (pin "2") (pinfunction "2_2") (pintype "passive"))
      (node (ref "R5553") (pin "1") (pinfunction "1_1") (pintype "passive"))
      (node (ref "U5500") (pin "22") (pinfunction "IVDD12_22_22") (pintype "passive"))
      (node (ref "U5500") (pin "28") (pinfunction "IVDD12_28_28") (pintype "passive"))
      (node (ref "U5500") (pin "42") (pinfunction "IVDD12_42_42") (pintype "passive"))
      (node (ref "U5500") (pin "43") (pinfunction "IVDD12_43_43") (pintype "passive"))
      (node (ref "U5500") (pin "51") (pinfunction "IVDD12_51_51") (pintype "passive"))
      (node (ref "U5500") (pin "52") (pinfunction "IVDD12_52_52") (pintype "passive"))
    )
    (net (code "84") (name "VDD_NVDD12_6161") (class "Default")
      (node (ref "C5528") (pin "1") (pinfunction "1_1") (pintype "passive"))
      (node (ref "C5529") (pin "1") (pinfunction "1_1") (pintype "passive"))
      (node (ref "C5530") (pin "1") (pinfunction "1_1") (pintype "passive"))
      (node (ref "FB5504") (pin "2") (pinfunction "2_2") (pintype "passive"))
      (node (ref "U5500") (pin "14") (pinfunction "NVDD12_14_14") (pintype "passive"))
      (node (ref "U5500") (pin "3") (pinfunction "NVDD12_3_3") (pintype "passive"))
    )
    (net (code "85") (name "VDD_PVCC12_6161") (class "Default")
      (node (ref "C5516") (pin "1") (pinfunction "1_1") (pintype "passive"))
      (node (ref "C5517") (pin "1") (pinfunction "1_1") (pintype "passive"))
      (node (ref "FB5502") (pin "2") (pinfunction "2_2") (pintype "passive"))
      (node (ref "U5500") (pin "29") (pinfunction "PVCC12_29_29") (pintype "passive"))
    )
    (net (code "86") (name "VDD_RDVDD12_6161") (class "Default")
      (node (ref "C5532") (pin "1") (pinfunction "1_1") (pintype "passive"))
      (node (ref "C5533") (pin "1") (pinfunction "1_1") (pintype "passive"))
      (node (ref "FB5505") (pin "2") (pinfunction "2_2") (pintype "passive"))
      (node (ref "U5500") (pin "2") (pinfunction "RDVDD12_2") (pintype "passive"))
    )
    (net (code "87") (name "VDD_TDVDD12_6161") (class "Default")
      (node (ref "C5518") (pin "1") (pinfunction "1_1") (pintype "passive"))
      (node (ref "C5519") (pin "1") (pinfunction "1_1") (pintype "passive"))
      (node (ref "FB5503") (pin "2") (pinfunction "2_2") (pintype "passive"))
      (node (ref "U5500") (pin "39") (pinfunction "TDVDD12_39_39") (pintype "passive"))
    )
    (net (code "88") (name "unconnected-(J5500-Utility-Pad14)") (class "Default")
      (node (ref "J5500") (pin "14") (pinfunction "Utility_14") (pintype "passive+no_connect"))
    )
  )
)
